# Preselector.net
KiCad netlist of a schematic drawn in EAGLE
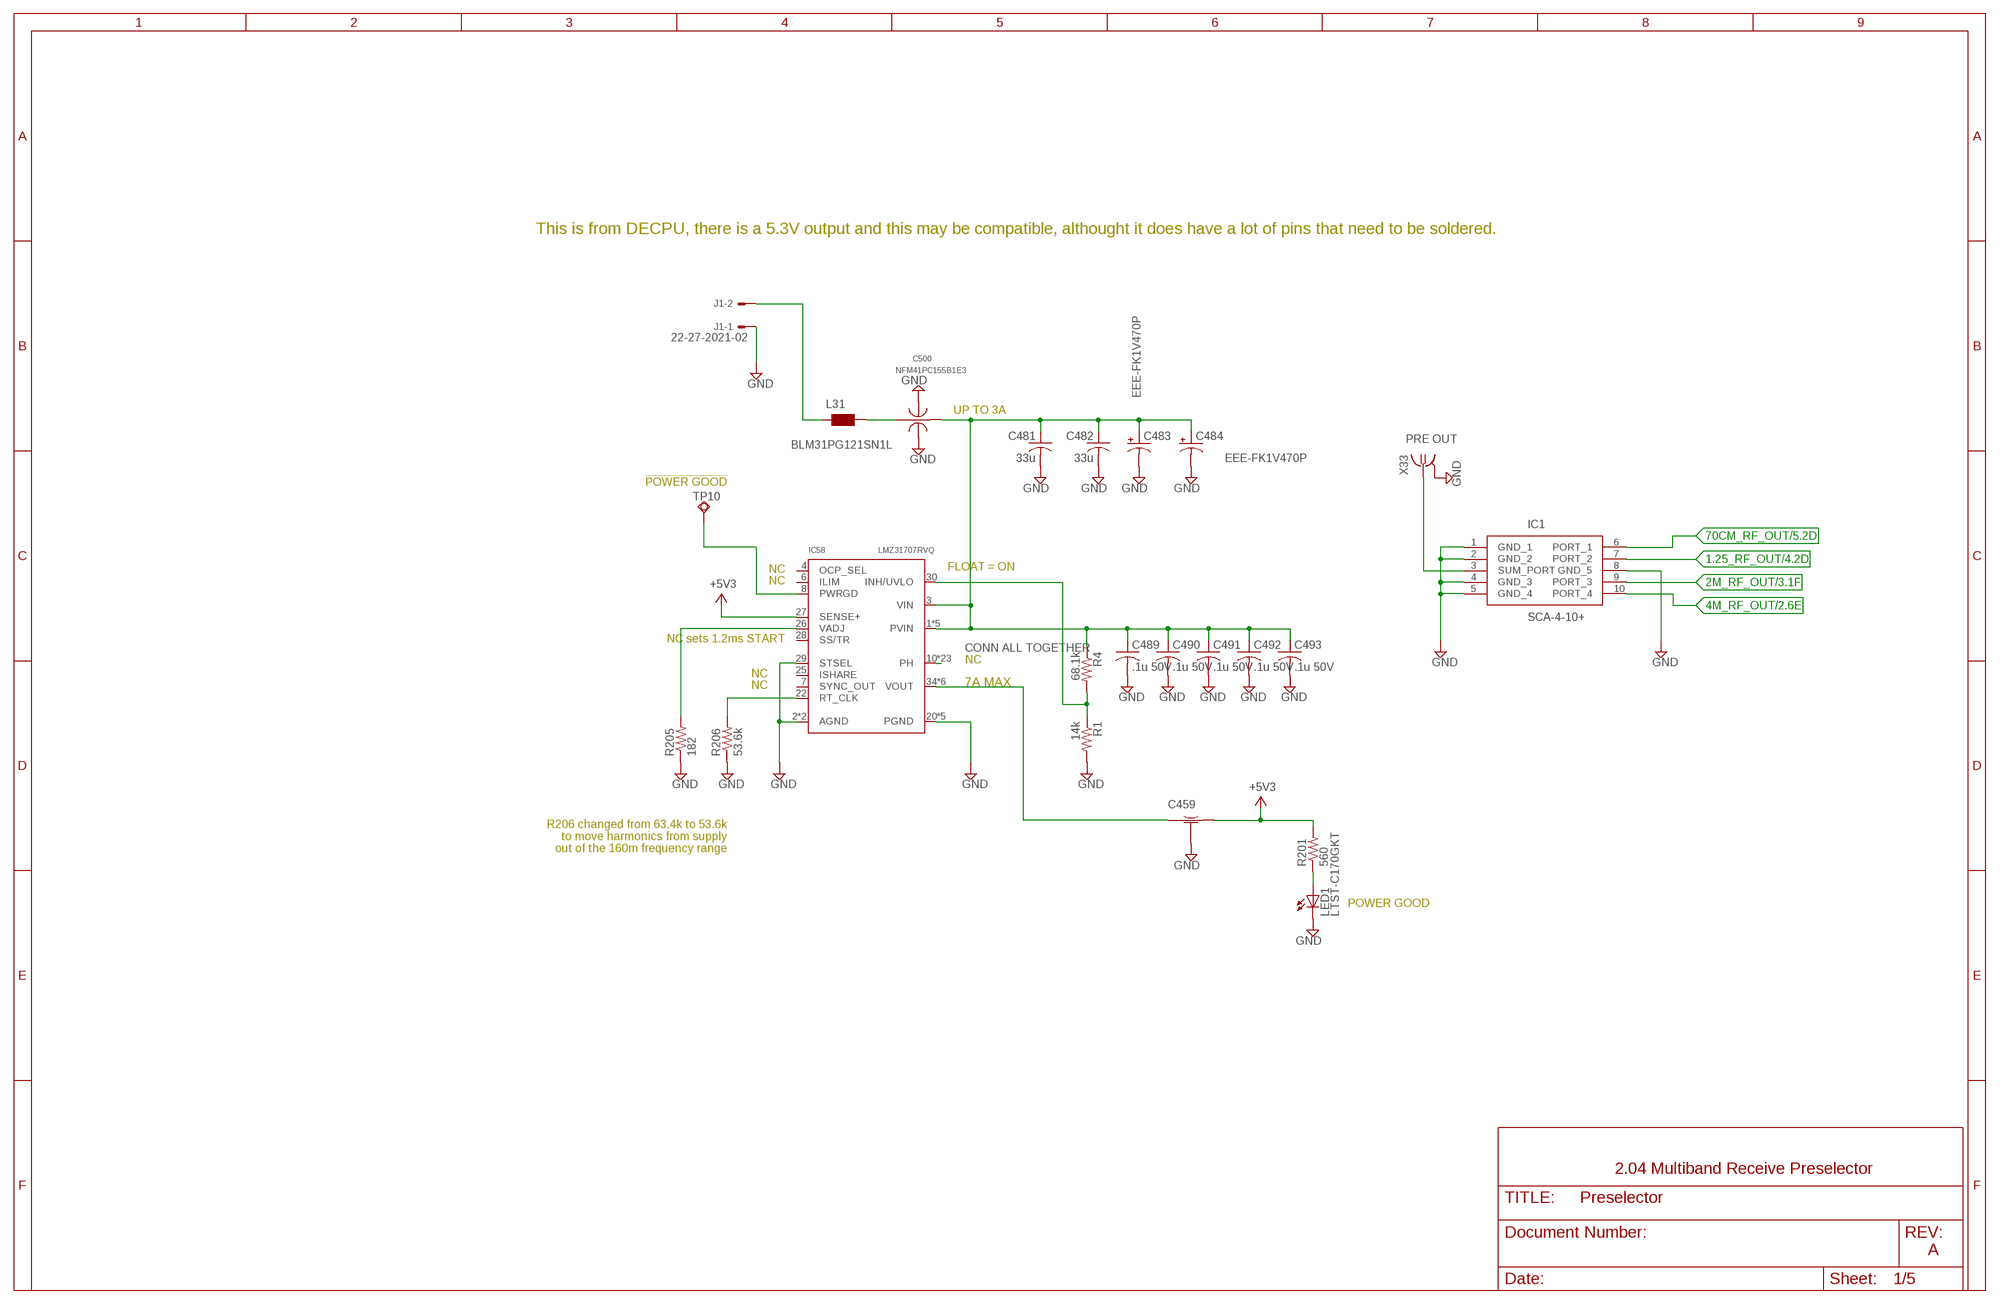
[diagram p0: schematic, sheet 1]
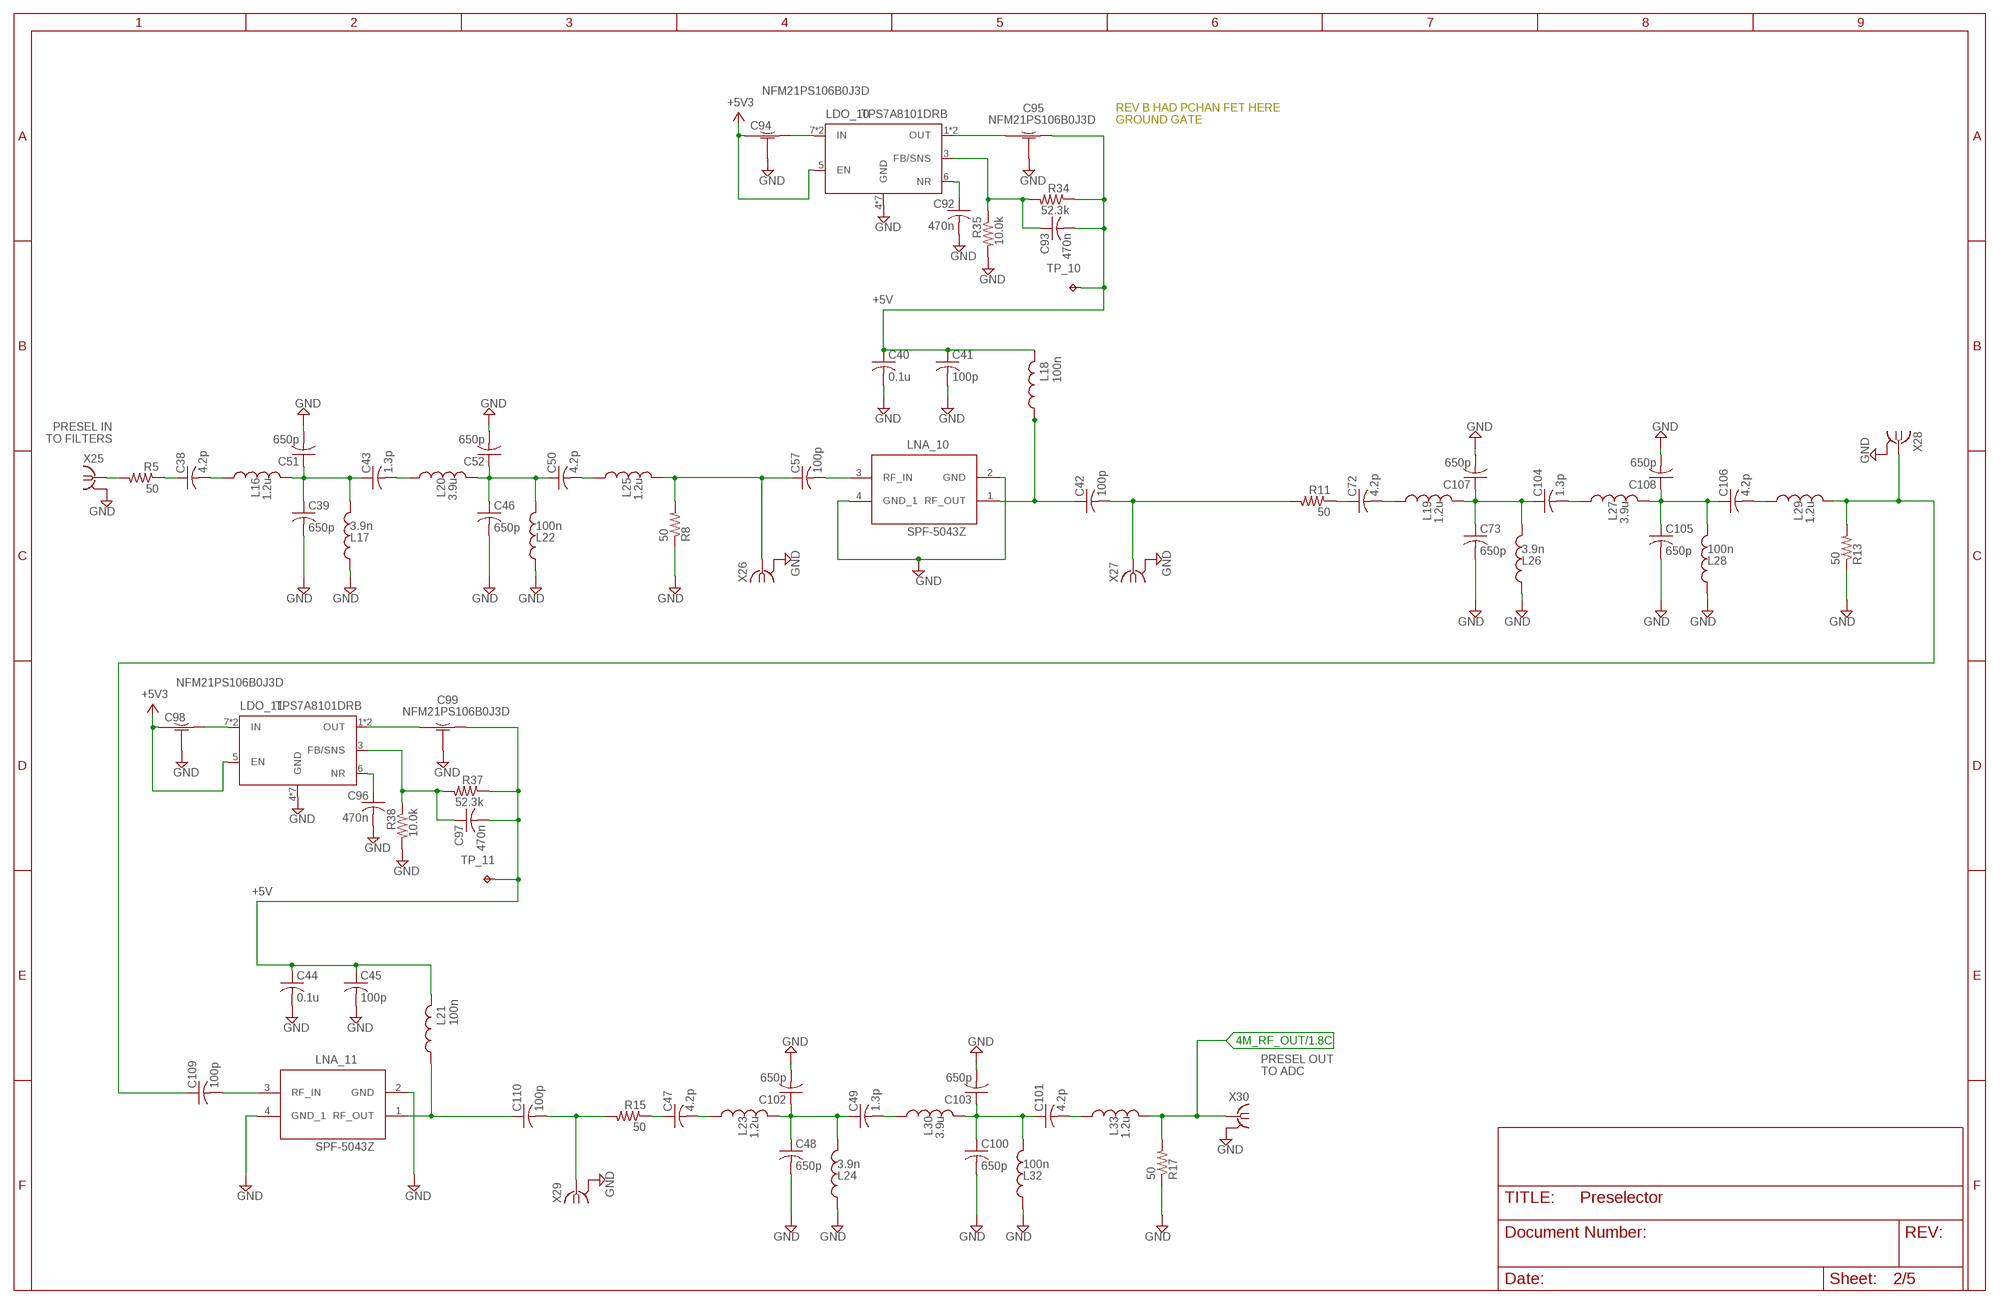
[diagram p1: schematic, sheet 2]
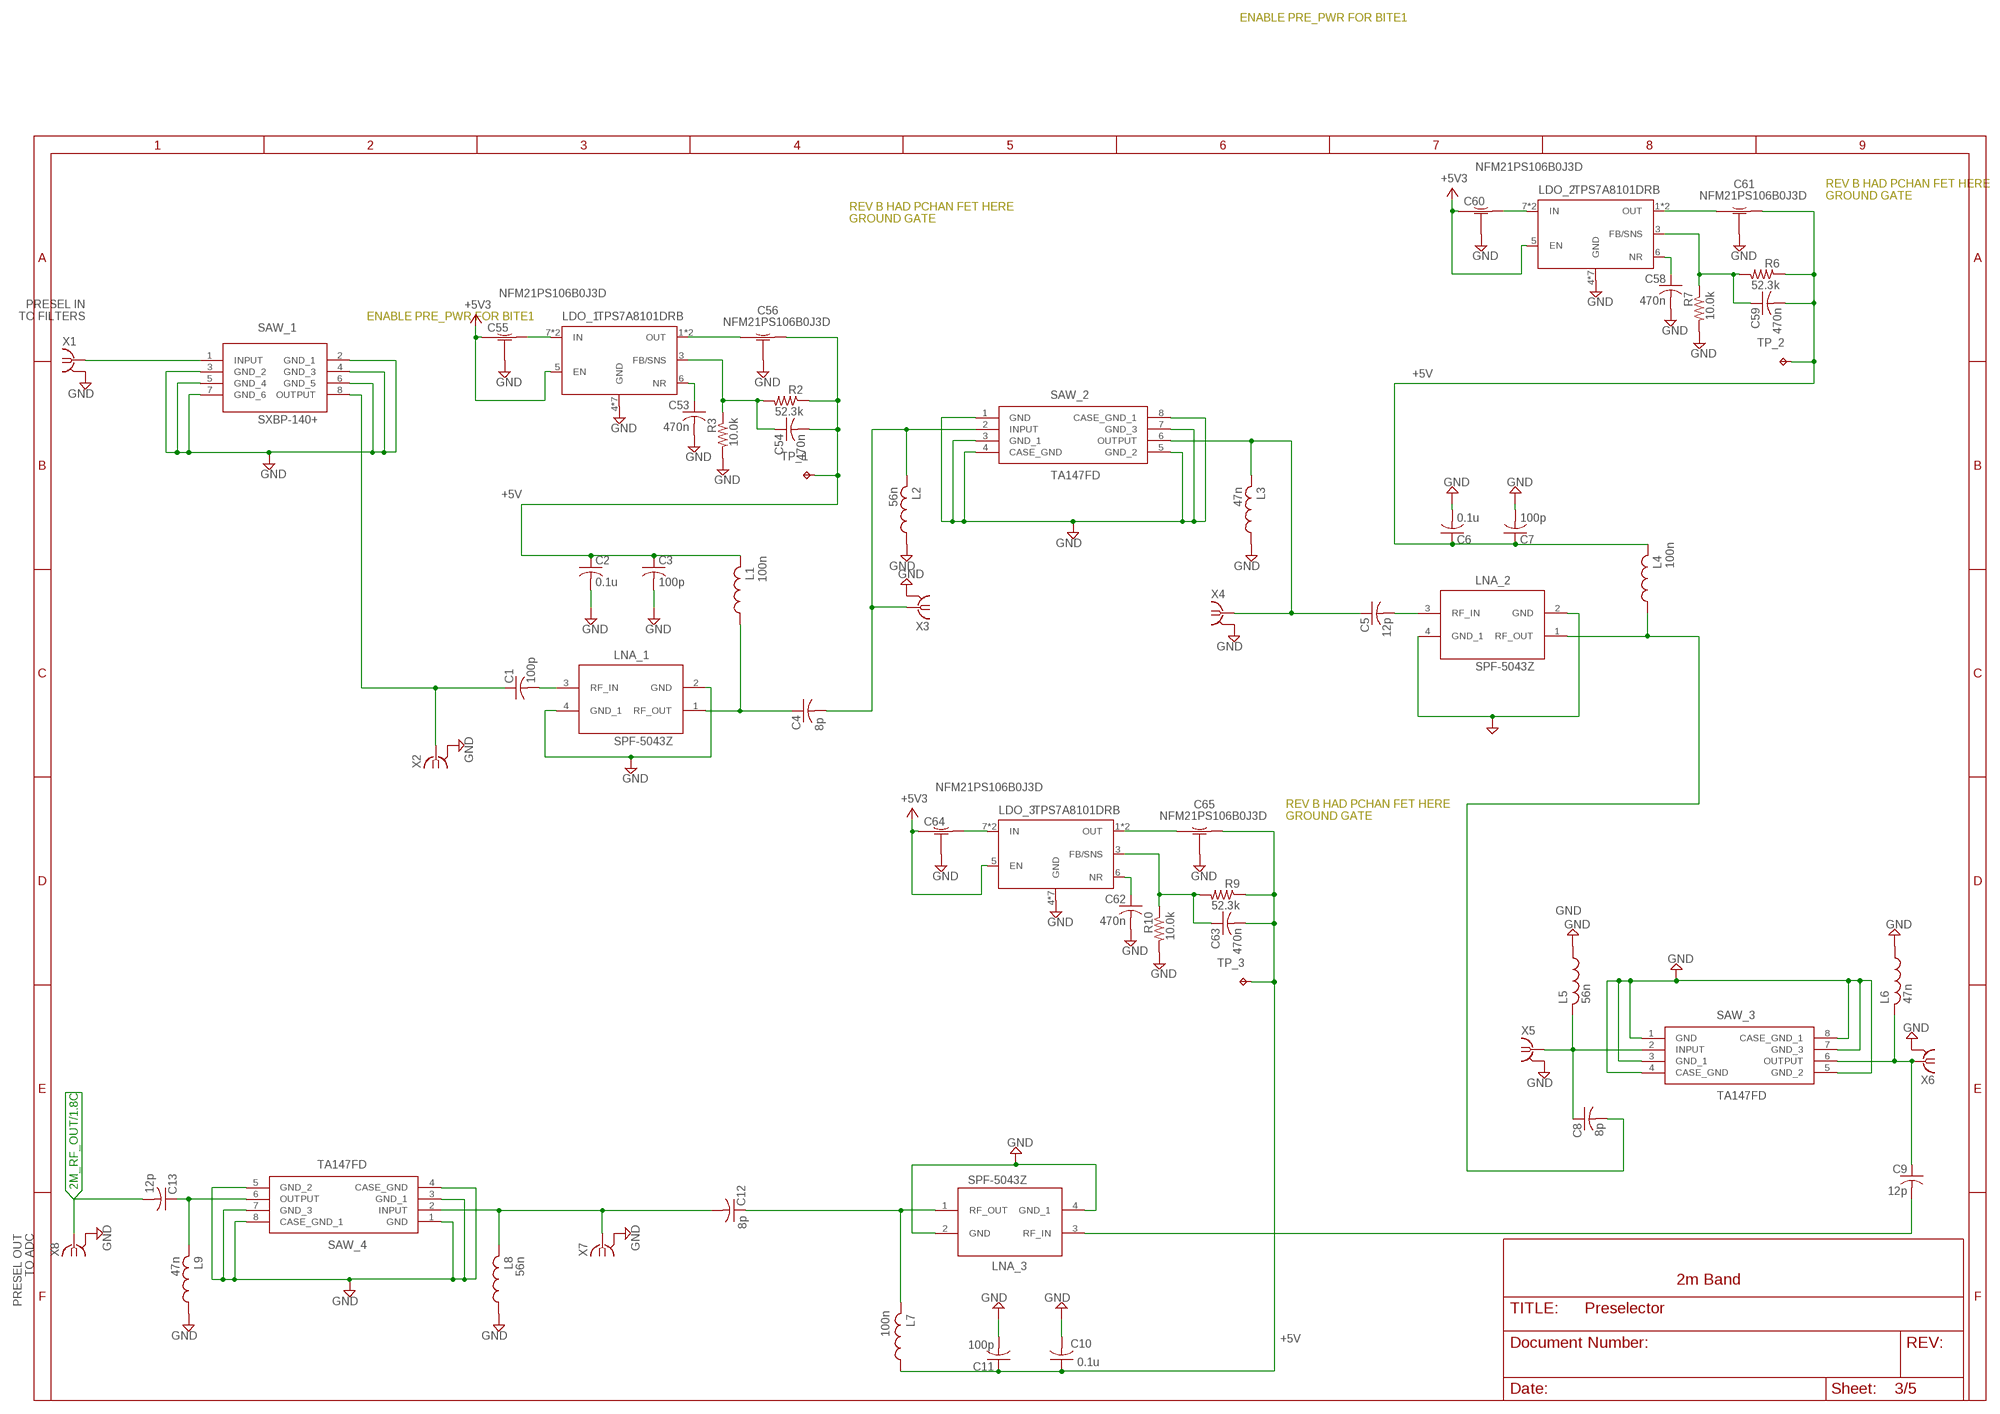
[diagram p2: schematic, sheet 3]
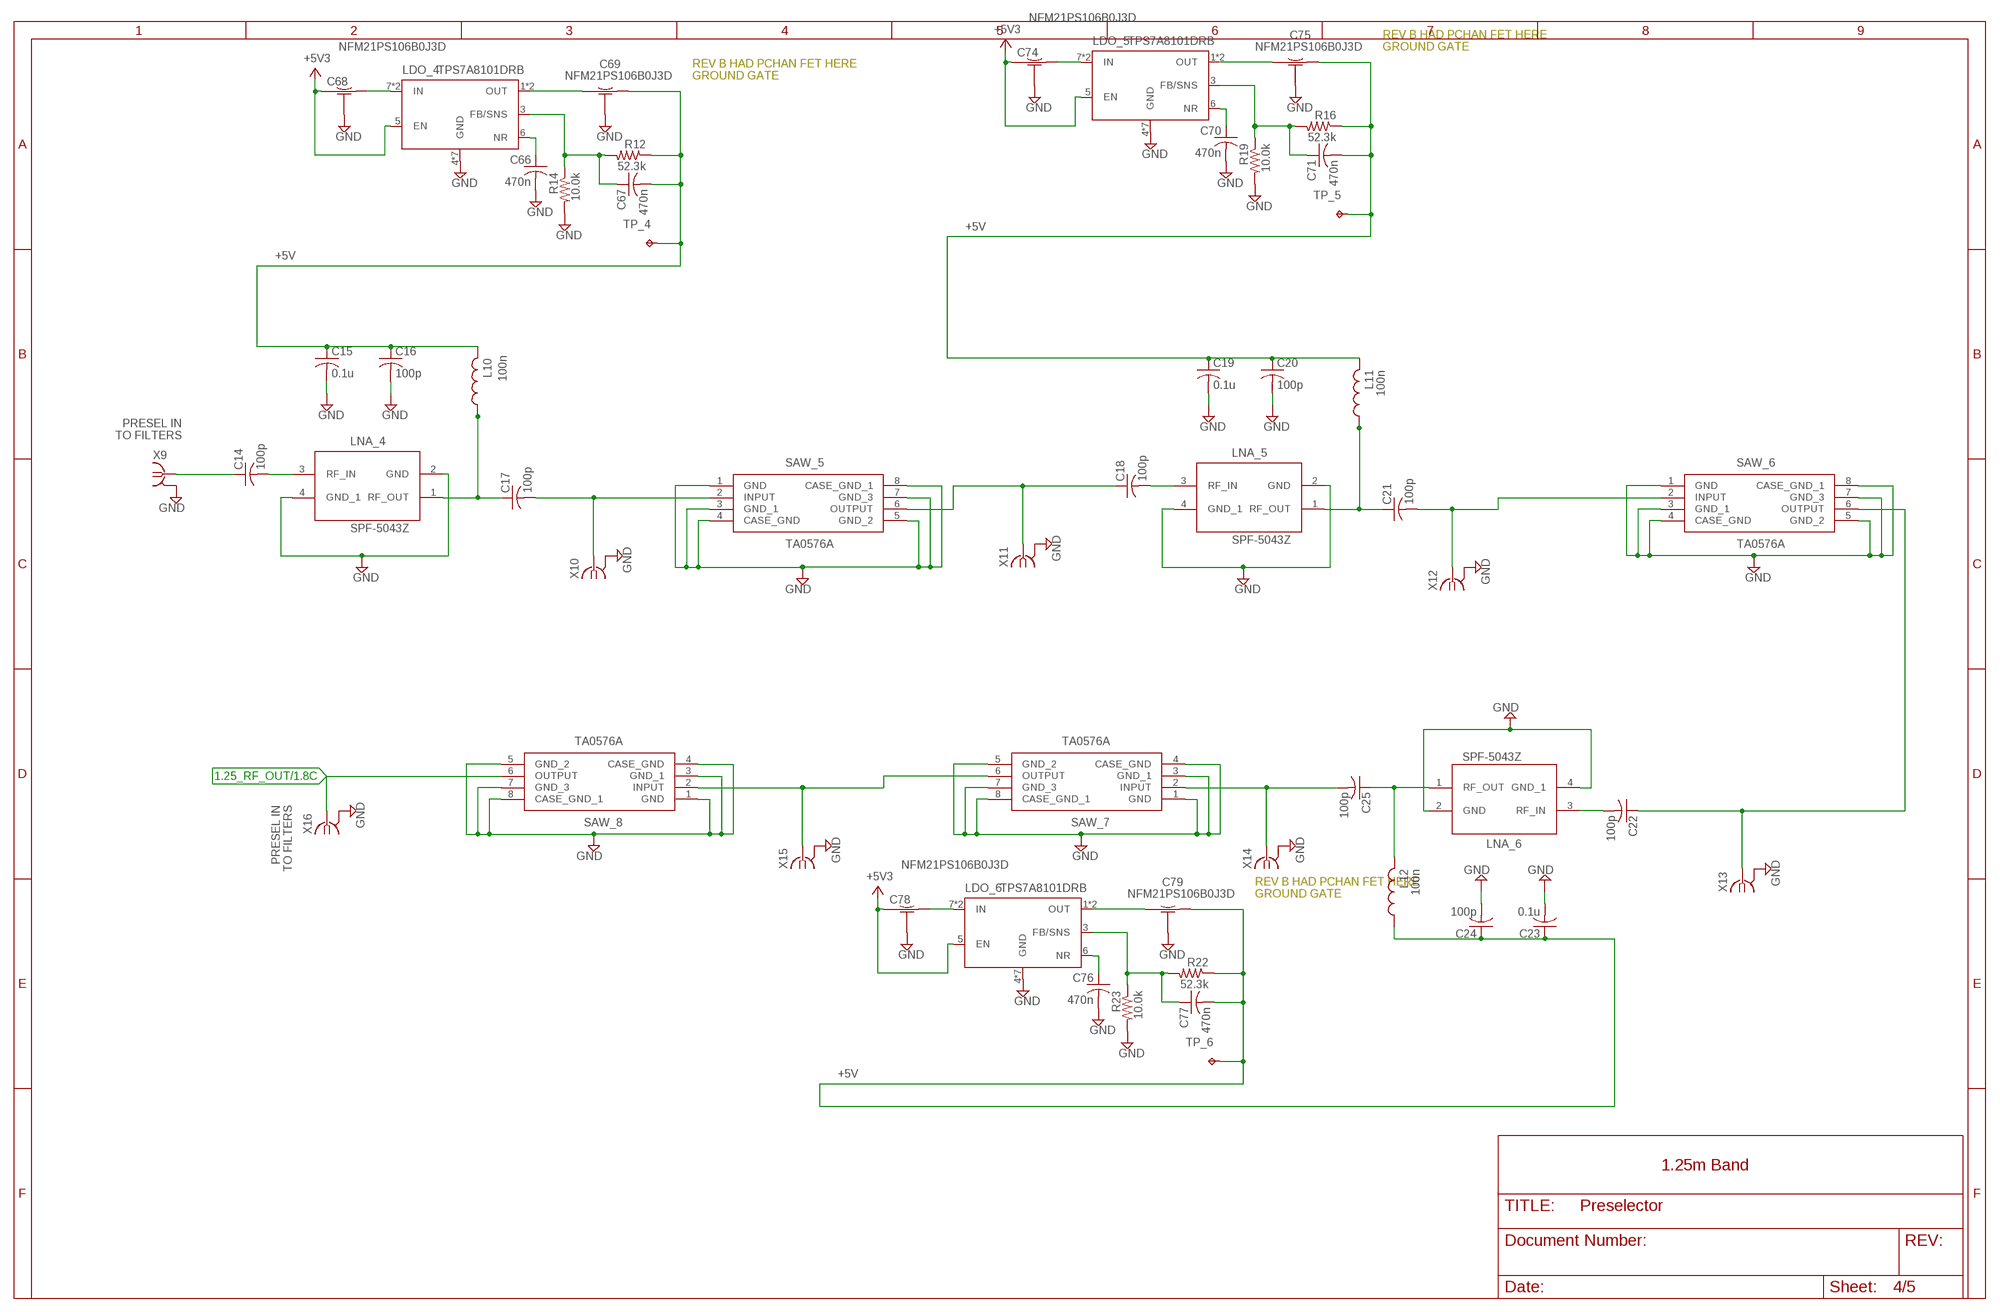
[diagram p3: schematic, sheet 4]
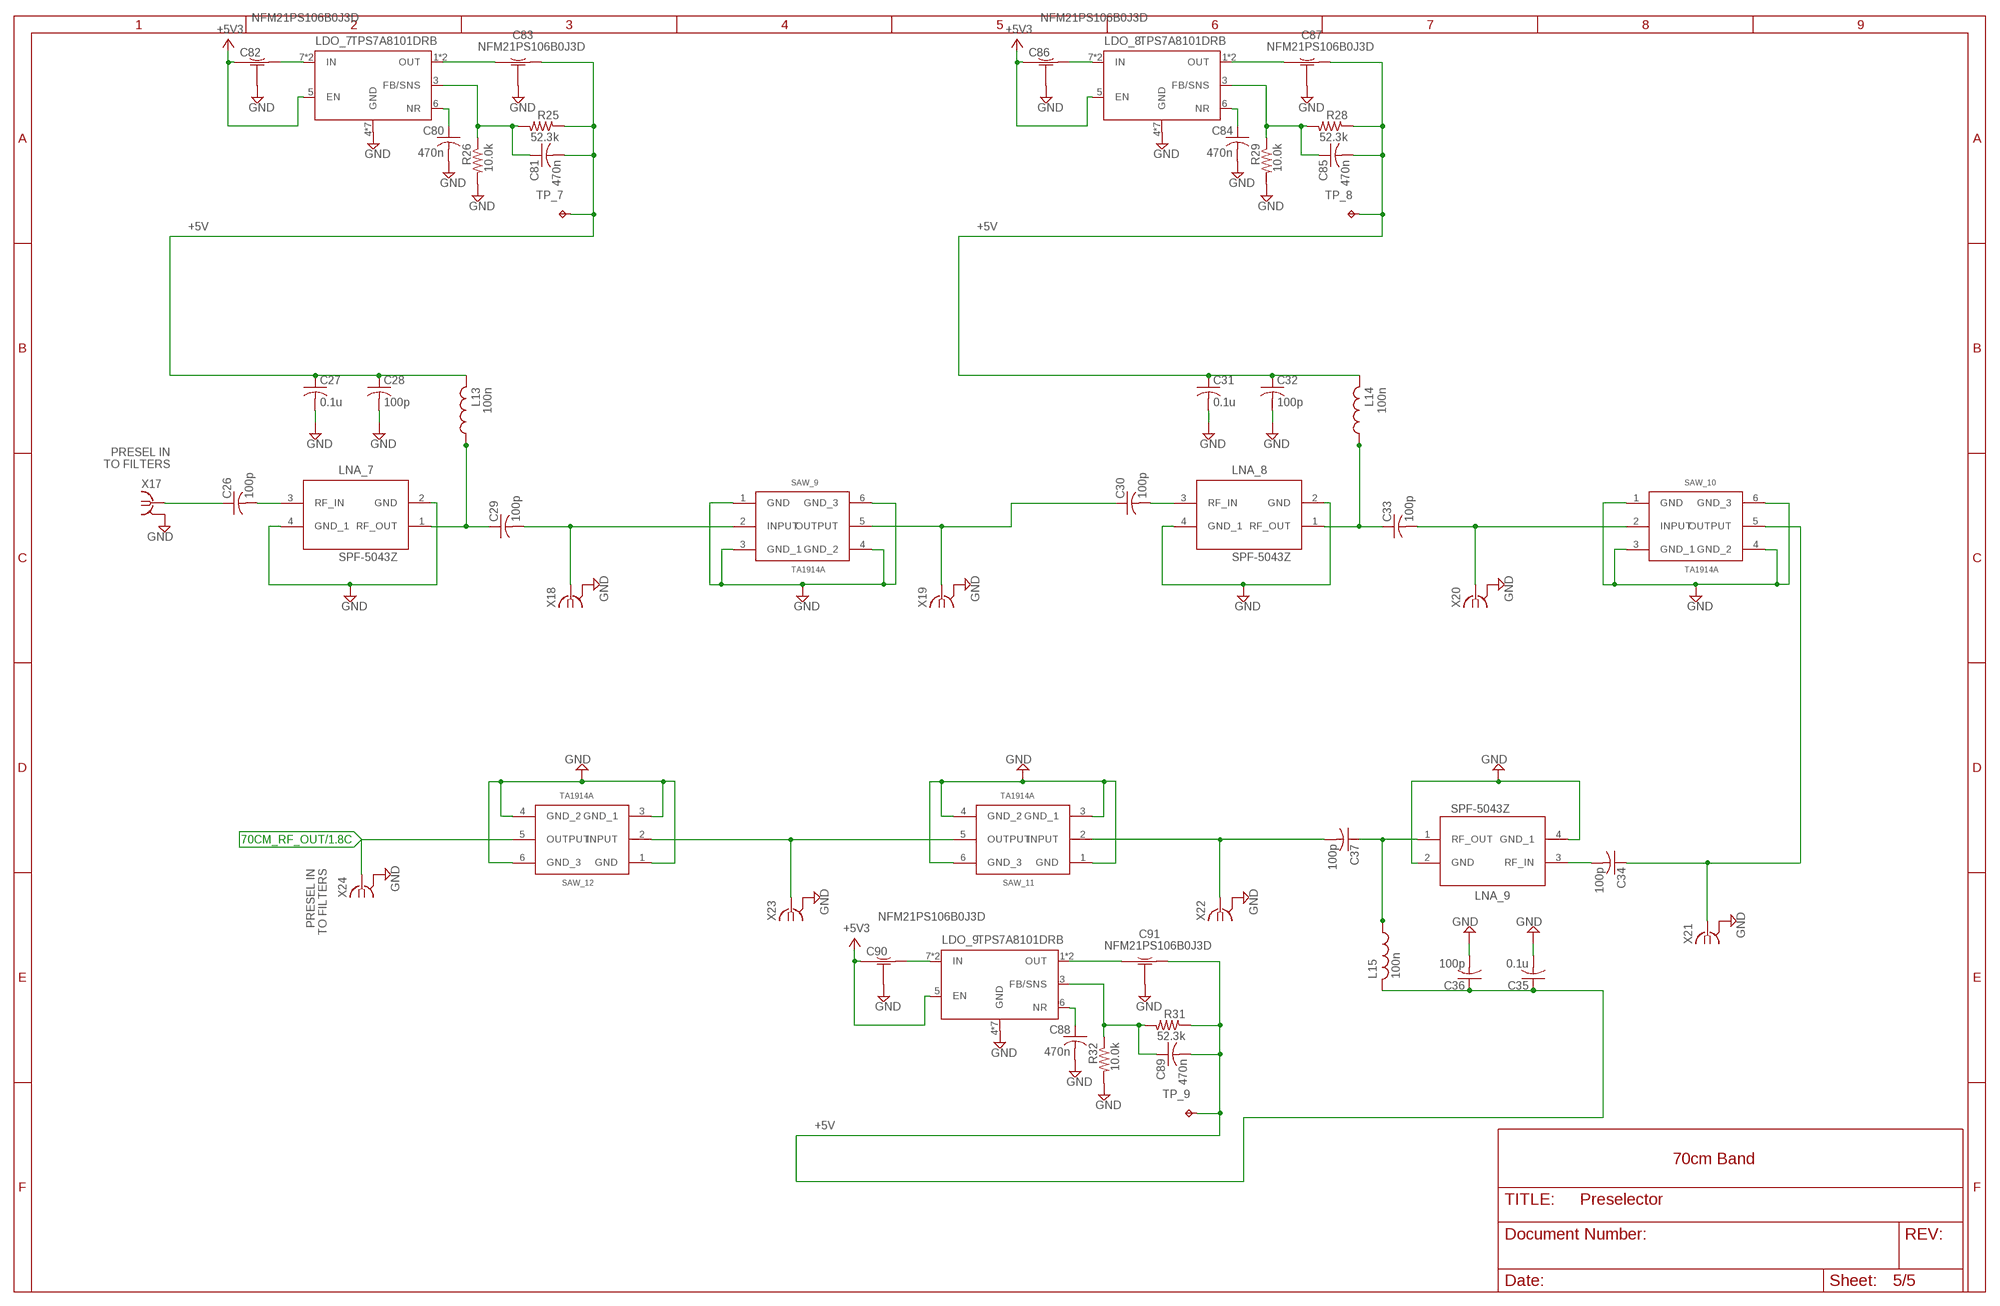
[diagram p4: schematic, sheet 5]

(export (version "E")
  (design (tool "Eeschema 10.0.6"))
  (components
    (comp (ref "C14")
      (value "100p")
      (footprint "eagle-import:C0603K")
      (libsource (lib "eagle-import") (part "C-USC0603K"))
    )
    (comp (ref "C15")
      (value "0.1u")
      (footprint "eagle-import:C0603K")
      (libsource (lib "eagle-import") (part "C-USC0603K"))
    )
    (comp (ref "C16")
      (value "100p")
      (footprint "eagle-import:C0603K")
      (libsource (lib "eagle-import") (part "C-USC0603K"))
    )
    (comp (ref "C17")
      (value "100p")
      (footprint "eagle-import:C0603K")
      (libsource (lib "eagle-import") (part "C-USC0603K"))
    )
    (comp (ref "C18")
      (value "100p")
      (footprint "eagle-import:C0603K")
      (libsource (lib "eagle-import") (part "C-USC0603K"))
    )
    (comp (ref "C19")
      (value "0.1u")
      (footprint "eagle-import:C0603K")
      (libsource (lib "eagle-import") (part "C-USC0603K"))
    )
    (comp (ref "C20")
      (value "100p")
      (footprint "eagle-import:C0603K")
      (libsource (lib "eagle-import") (part "C-USC0603K"))
    )
    (comp (ref "C21")
      (value "100p")
      (footprint "eagle-import:C0603K")
      (libsource (lib "eagle-import") (part "C-USC0603K"))
    )
    (comp (ref "C22")
      (value "100p")
      (footprint "eagle-import:C0603K")
      (libsource (lib "eagle-import") (part "C-USC0603K"))
    )
    (comp (ref "C23")
      (value "0.1u")
      (footprint "eagle-import:C0603K")
      (libsource (lib "eagle-import") (part "C-USC0603K"))
    )
    (comp (ref "C24")
      (value "100p")
      (footprint "eagle-import:C0603K")
      (libsource (lib "eagle-import") (part "C-USC0603K"))
    )
    (comp (ref "C25")
      (value "100p")
      (footprint "eagle-import:C0603K")
      (libsource (lib "eagle-import") (part "C-USC0603K"))
    )
    (comp (ref "C66")
      (value "470n")
      (footprint "eagle-import:C0603K")
      (libsource (lib "eagle-import") (part "C-USC0603K"))
    )
    (comp (ref "C67")
      (value "470n")
      (footprint "eagle-import:C0603K")
      (libsource (lib "eagle-import") (part "C-USC0603K"))
    )
    (comp (ref "C68")
      (value "NFM21PS106B0J3D")
      (footprint "eagle-import:NFM21PS")
      (libsource (lib "eagle-import") (part "NFM21PS"))
    )
    (comp (ref "C69")
      (value "NFM21PS106B0J3D")
      (footprint "eagle-import:NFM21PS")
      (libsource (lib "eagle-import") (part "NFM21PS"))
    )
    (comp (ref "C70")
      (value "470n")
      (footprint "eagle-import:C0603K")
      (libsource (lib "eagle-import") (part "C-USC0603K"))
    )
    (comp (ref "C71")
      (value "470n")
      (footprint "eagle-import:C0603K")
      (libsource (lib "eagle-import") (part "C-USC0603K"))
    )
    (comp (ref "C74")
      (value "NFM21PS106B0J3D")
      (footprint "eagle-import:NFM21PS")
      (libsource (lib "eagle-import") (part "NFM21PS"))
    )
    (comp (ref "C75")
      (value "NFM21PS106B0J3D")
      (footprint "eagle-import:NFM21PS")
      (libsource (lib "eagle-import") (part "NFM21PS"))
    )
    (comp (ref "C76")
      (value "470n")
      (footprint "eagle-import:C0603K")
      (libsource (lib "eagle-import") (part "C-USC0603K"))
    )
    (comp (ref "C77")
      (value "470n")
      (footprint "eagle-import:C0603K")
      (libsource (lib "eagle-import") (part "C-USC0603K"))
    )
    (comp (ref "C78")
      (value "NFM21PS106B0J3D")
      (footprint "eagle-import:NFM21PS")
      (libsource (lib "eagle-import") (part "NFM21PS"))
    )
    (comp (ref "C79")
      (value "NFM21PS106B0J3D")
      (footprint "eagle-import:NFM21PS")
      (libsource (lib "eagle-import") (part "NFM21PS"))
    )
    (comp (ref "L10")
      (value "100n")
      (footprint "eagle-import:C1206")
      (libsource (lib "eagle-import") (part "L-US1206"))
    )
    (comp (ref "L11")
      (value "100n")
      (footprint "eagle-import:C1206")
      (libsource (lib "eagle-import") (part "L-US1206"))
    )
    (comp (ref "L12")
      (value "100n")
      (footprint "eagle-import:C1206")
      (libsource (lib "eagle-import") (part "L-US1206"))
    )
    (comp (ref "LDO_4")
      (value "TPS7A8101DRB")
      (footprint "eagle-import:DRB")
      (libsource (lib "eagle-import") (part "TPS7A8101DRB"))
    )
    (comp (ref "LDO_5")
      (value "TPS7A8101DRB")
      (footprint "eagle-import:DRB")
      (libsource (lib "eagle-import") (part "TPS7A8101DRB"))
    )
    (comp (ref "LDO_6")
      (value "TPS7A8101DRB")
      (footprint "eagle-import:DRB")
      (libsource (lib "eagle-import") (part "TPS7A8101DRB"))
    )
    (comp (ref "LNA_4")
      (value "SPF-5043Z")
      (footprint "eagle-import:SPF-5043Z")
      (libsource (lib "eagle-import") (part "SPF-5043Z"))
    )
    (comp (ref "LNA_5")
      (value "SPF-5043Z")
      (footprint "eagle-import:SPF-5043Z")
      (libsource (lib "eagle-import") (part "SPF-5043Z"))
    )
    (comp (ref "LNA_6")
      (value "SPF-5043Z")
      (footprint "eagle-import:SPF-5043Z")
      (libsource (lib "eagle-import") (part "SPF-5043Z"))
    )
    (comp (ref "R12")
      (value "52.3k")
      (footprint "eagle-import:R0603")
      (libsource (lib "eagle-import") (part "R-US_R0603"))
    )
    (comp (ref "R14")
      (value "10.0k")
      (footprint "eagle-import:R0603")
      (libsource (lib "eagle-import") (part "R-US_R0603"))
    )
    (comp (ref "R16")
      (value "52.3k")
      (footprint "eagle-import:R0603")
      (libsource (lib "eagle-import") (part "R-US_R0603"))
    )
    (comp (ref "R19")
      (value "10.0k")
      (footprint "eagle-import:R0603")
      (libsource (lib "eagle-import") (part "R-US_R0603"))
    )
    (comp (ref "R22")
      (value "52.3k")
      (footprint "eagle-import:R0603")
      (libsource (lib "eagle-import") (part "R-US_R0603"))
    )
    (comp (ref "R23")
      (value "10.0k")
      (footprint "eagle-import:R0603")
      (libsource (lib "eagle-import") (part "R-US_R0603"))
    )
    (comp (ref "SAW_5")
      (value "TA0576A")
      (footprint "eagle-import:TA0576A")
      (libsource (lib "eagle-import") (part "TA0576A"))
    )
    (comp (ref "SAW_6")
      (value "TA0576A")
      (footprint "eagle-import:TA0576A")
      (libsource (lib "eagle-import") (part "TA0576A"))
    )
    (comp (ref "SAW_7")
      (value "TA0576A")
      (footprint "eagle-import:TA0576A")
      (libsource (lib "eagle-import") (part "TA0576A"))
    )
    (comp (ref "SAW_8")
      (value "TA0576A")
      (footprint "eagle-import:TA0576A")
      (libsource (lib "eagle-import") (part "TA0576A"))
    )
    (comp (ref "TP_4")
      (value "TPTP20SQ")
      (footprint "eagle-import:TP20SQ")
      (libsource (lib "eagle-import") (part "TPTP20SQ"))
    )
    (comp (ref "TP_5")
      (value "TPTP20SQ")
      (footprint "eagle-import:TP20SQ")
      (libsource (lib "eagle-import") (part "TPTP20SQ"))
    )
    (comp (ref "TP_6")
      (value "TPTP20SQ")
      (footprint "eagle-import:TP20SQ")
      (libsource (lib "eagle-import") (part "TPTP20SQ"))
    )
    (comp (ref "X9")
      (value "0733660061")
      (footprint "eagle-import:BU-SMA-V")
      (libsource (lib "eagle-import") (part "BU-SMA-V"))
    )
    (comp (ref "X10")
      (value "0733660061")
      (footprint "eagle-import:BU-SMA-V")
      (libsource (lib "eagle-import") (part "BU-SMA-V"))
    )
    (comp (ref "X11")
      (value "0733660061")
      (footprint "eagle-import:BU-SMA-V")
      (libsource (lib "eagle-import") (part "BU-SMA-V"))
    )
    (comp (ref "X12")
      (value "0733660061")
      (footprint "eagle-import:BU-SMA-V")
      (libsource (lib "eagle-import") (part "BU-SMA-V"))
    )
    (comp (ref "X13")
      (value "0733660061")
      (footprint "eagle-import:BU-SMA-V")
      (libsource (lib "eagle-import") (part "BU-SMA-V"))
    )
    (comp (ref "X14")
      (value "0733660061")
      (footprint "eagle-import:BU-SMA-V")
      (libsource (lib "eagle-import") (part "BU-SMA-V"))
    )
    (comp (ref "X15")
      (value "0733660061")
      (footprint "eagle-import:BU-SMA-V")
      (libsource (lib "eagle-import") (part "BU-SMA-V"))
    )
    (comp (ref "X16")
      (value "0733660061")
      (footprint "eagle-import:BU-SMA-V")
      (libsource (lib "eagle-import") (part "BU-SMA-V"))
    )
    (comp (ref "C38")
      (value "4.2p")
      (footprint "eagle-import:C0603K")
      (libsource (lib "eagle-import") (part "C-USC0603K"))
    )
    (comp (ref "C39")
      (value "650p")
      (footprint "eagle-import:C0603K")
      (libsource (lib "eagle-import") (part "C-USC0603K"))
    )
    (comp (ref "C40")
      (value "0.1u")
      (footprint "eagle-import:C0603K")
      (libsource (lib "eagle-import") (part "C-USC0603K"))
    )
    (comp (ref "C41")
      (value "100p")
      (footprint "eagle-import:C0603K")
      (libsource (lib "eagle-import") (part "C-USC0603K"))
    )
    (comp (ref "C42")
      (value "100p")
      (footprint "eagle-import:C0603K")
      (libsource (lib "eagle-import") (part "C-USC0603K"))
    )
    (comp (ref "C43")
      (value "1.3p")
      (footprint "eagle-import:C0603K")
      (libsource (lib "eagle-import") (part "C-USC0603K"))
    )
    (comp (ref "C44")
      (value "0.1u")
      (footprint "eagle-import:C0603K")
      (libsource (lib "eagle-import") (part "C-USC0603K"))
    )
    (comp (ref "C45")
      (value "100p")
      (footprint "eagle-import:C0603K")
      (libsource (lib "eagle-import") (part "C-USC0603K"))
    )
    (comp (ref "C46")
      (value "650p")
      (footprint "eagle-import:C0603K")
      (libsource (lib "eagle-import") (part "C-USC0603K"))
    )
    (comp (ref "C47")
      (value "4.2p")
      (footprint "eagle-import:C0603K")
      (libsource (lib "eagle-import") (part "C-USC0603K"))
    )
    (comp (ref "C48")
      (value "650p")
      (footprint "eagle-import:C0603K")
      (libsource (lib "eagle-import") (part "C-USC0603K"))
    )
    (comp (ref "C49")
      (value "1.3p")
      (footprint "eagle-import:C0603K")
      (libsource (lib "eagle-import") (part "C-USC0603K"))
    )
    (comp (ref "C50")
      (value "4.2p")
      (footprint "eagle-import:C0603K")
      (libsource (lib "eagle-import") (part "C-USC0603K"))
    )
    (comp (ref "C51")
      (value "650p")
      (footprint "eagle-import:C0603K")
      (libsource (lib "eagle-import") (part "C-USC0603K"))
    )
    (comp (ref "C52")
      (value "650p")
      (footprint "eagle-import:C0603K")
      (libsource (lib "eagle-import") (part "C-USC0603K"))
    )
    (comp (ref "C57")
      (value "100p")
      (footprint "eagle-import:C0603K")
      (libsource (lib "eagle-import") (part "C-USC0603K"))
    )
    (comp (ref "C72")
      (value "4.2p")
      (footprint "eagle-import:C0603K")
      (libsource (lib "eagle-import") (part "C-USC0603K"))
    )
    (comp (ref "C73")
      (value "650p")
      (footprint "eagle-import:C0603K")
      (libsource (lib "eagle-import") (part "C-USC0603K"))
    )
    (comp (ref "C92")
      (value "470n")
      (footprint "eagle-import:C0603K")
      (libsource (lib "eagle-import") (part "C-USC0603K"))
    )
    (comp (ref "C93")
      (value "470n")
      (footprint "eagle-import:C0603K")
      (libsource (lib "eagle-import") (part "C-USC0603K"))
    )
    (comp (ref "C94")
      (value "NFM21PS106B0J3D")
      (footprint "eagle-import:NFM21PS")
      (libsource (lib "eagle-import") (part "NFM21PS"))
    )
    (comp (ref "C95")
      (value "NFM21PS106B0J3D")
      (footprint "eagle-import:NFM21PS")
      (libsource (lib "eagle-import") (part "NFM21PS"))
    )
    (comp (ref "C96")
      (value "470n")
      (footprint "eagle-import:C0603K")
      (libsource (lib "eagle-import") (part "C-USC0603K"))
    )
    (comp (ref "C97")
      (value "470n")
      (footprint "eagle-import:C0603K")
      (libsource (lib "eagle-import") (part "C-USC0603K"))
    )
    (comp (ref "C98")
      (value "NFM21PS106B0J3D")
      (footprint "eagle-import:NFM21PS")
      (libsource (lib "eagle-import") (part "NFM21PS"))
    )
    (comp (ref "C99")
      (value "NFM21PS106B0J3D")
      (footprint "eagle-import:NFM21PS")
      (libsource (lib "eagle-import") (part "NFM21PS"))
    )
    (comp (ref "C100")
      (value "650p")
      (footprint "eagle-import:C0603K")
      (libsource (lib "eagle-import") (part "C-USC0603K"))
    )
    (comp (ref "C101")
      (value "4.2p")
      (footprint "eagle-import:C0603K")
      (libsource (lib "eagle-import") (part "C-USC0603K"))
    )
    (comp (ref "C102")
      (value "650p")
      (footprint "eagle-import:C0603K")
      (libsource (lib "eagle-import") (part "C-USC0603K"))
    )
    (comp (ref "C103")
      (value "650p")
      (footprint "eagle-import:C0603K")
      (libsource (lib "eagle-import") (part "C-USC0603K"))
    )
    (comp (ref "C104")
      (value "1.3p")
      (footprint "eagle-import:C0603K")
      (libsource (lib "eagle-import") (part "C-USC0603K"))
    )
    (comp (ref "C105")
      (value "650p")
      (footprint "eagle-import:C0603K")
      (libsource (lib "eagle-import") (part "C-USC0603K"))
    )
    (comp (ref "C106")
      (value "4.2p")
      (footprint "eagle-import:C0603K")
      (libsource (lib "eagle-import") (part "C-USC0603K"))
    )
    (comp (ref "C107")
      (value "650p")
      (footprint "eagle-import:C0603K")
      (libsource (lib "eagle-import") (part "C-USC0603K"))
    )
    (comp (ref "C108")
      (value "650p")
      (footprint "eagle-import:C0603K")
      (libsource (lib "eagle-import") (part "C-USC0603K"))
    )
    (comp (ref "C109")
      (value "100p")
      (footprint "eagle-import:C0603K")
      (libsource (lib "eagle-import") (part "C-USC0603K"))
    )
    (comp (ref "C110")
      (value "100p")
      (footprint "eagle-import:C0603K")
      (libsource (lib "eagle-import") (part "C-USC0603K"))
    )
    (comp (ref "L16")
      (value "1.2u")
      (footprint "eagle-import:C0603K")
      (libsource (lib "eagle-import") (part "L-US0603"))
    )
    (comp (ref "L17")
      (value "3.9n")
      (footprint "eagle-import:C0603K")
      (libsource (lib "eagle-import") (part "L-US0603"))
    )
    (comp (ref "L18")
      (value "100n")
      (footprint "eagle-import:C1206")
      (libsource (lib "eagle-import") (part "L-US1206"))
    )
    (comp (ref "L19")
      (value "1.2u")
      (footprint "eagle-import:C0603K")
      (libsource (lib "eagle-import") (part "L-US0603"))
    )
    (comp (ref "L20")
      (value "3.9u")
      (footprint "eagle-import:C0603K")
      (libsource (lib "eagle-import") (part "L-US0603"))
    )
    (comp (ref "L21")
      (value "100n")
      (footprint "eagle-import:C1206")
      (libsource (lib "eagle-import") (part "L-US1206"))
    )
    (comp (ref "L22")
      (value "100n")
      (footprint "eagle-import:C0603K")
      (libsource (lib "eagle-import") (part "L-US0603"))
    )
    (comp (ref "L23")
      (value "1.2u")
      (footprint "eagle-import:C0603K")
      (libsource (lib "eagle-import") (part "L-US0603"))
    )
    (comp (ref "L24")
      (value "3.9n")
      (footprint "eagle-import:C0603K")
      (libsource (lib "eagle-import") (part "L-US0603"))
    )
    (comp (ref "L25")
      (value "1.2u")
      (footprint "eagle-import:C0603K")
      (libsource (lib "eagle-import") (part "L-US0603"))
    )
    (comp (ref "L26")
      (value "3.9n")
      (footprint "eagle-import:C0603K")
      (libsource (lib "eagle-import") (part "L-US0603"))
    )
    (comp (ref "L27")
      (value "3.9u")
      (footprint "eagle-import:C0603K")
      (libsource (lib "eagle-import") (part "L-US0603"))
    )
    (comp (ref "L28")
      (value "100n")
      (footprint "eagle-import:C0603K")
      (libsource (lib "eagle-import") (part "L-US0603"))
    )
    (comp (ref "L29")
      (value "1.2u")
      (footprint "eagle-import:C0603K")
      (libsource (lib "eagle-import") (part "L-US0603"))
    )
    (comp (ref "L30")
      (value "3.9u")
      (footprint "eagle-import:C0603K")
      (libsource (lib "eagle-import") (part "L-US0603"))
    )
    (comp (ref "L32")
      (value "100n")
      (footprint "eagle-import:C0603K")
      (libsource (lib "eagle-import") (part "L-US0603"))
    )
    (comp (ref "L33")
      (value "1.2u")
      (footprint "eagle-import:C0603K")
      (libsource (lib "eagle-import") (part "L-US0603"))
    )
    (comp (ref "LDO_10")
      (value "TPS7A8101DRB")
      (footprint "eagle-import:DRB")
      (libsource (lib "eagle-import") (part "TPS7A8101DRB"))
    )
    (comp (ref "LDO_11")
      (value "TPS7A8101DRB")
      (footprint "eagle-import:DRB")
      (libsource (lib "eagle-import") (part "TPS7A8101DRB"))
    )
    (comp (ref "LNA_10")
      (value "SPF-5043Z")
      (footprint "eagle-import:SPF-5043Z")
      (libsource (lib "eagle-import") (part "SPF-5043Z"))
    )
    (comp (ref "LNA_11")
      (value "SPF-5043Z")
      (footprint "eagle-import:SPF-5043Z")
      (libsource (lib "eagle-import") (part "SPF-5043Z"))
    )
    (comp (ref "R5")
      (value "50")
      (footprint "eagle-import:R0603")
      (libsource (lib "eagle-import") (part "R-US_R0603"))
    )
    (comp (ref "R8")
      (value "50")
      (footprint "eagle-import:R0603")
      (libsource (lib "eagle-import") (part "R-US_R0603"))
    )
    (comp (ref "R11")
      (value "50")
      (footprint "eagle-import:R0603")
      (libsource (lib "eagle-import") (part "R-US_R0603"))
    )
    (comp (ref "R13")
      (value "50")
      (footprint "eagle-import:R0603")
      (libsource (lib "eagle-import") (part "R-US_R0603"))
    )
    (comp (ref "R15")
      (value "50")
      (footprint "eagle-import:R0603")
      (libsource (lib "eagle-import") (part "R-US_R0603"))
    )
    (comp (ref "R17")
      (value "50")
      (footprint "eagle-import:R0603")
      (libsource (lib "eagle-import") (part "R-US_R0603"))
    )
    (comp (ref "R34")
      (value "52.3k")
      (footprint "eagle-import:R0603")
      (libsource (lib "eagle-import") (part "R-US_R0603"))
    )
    (comp (ref "R35")
      (value "10.0k")
      (footprint "eagle-import:R0603")
      (libsource (lib "eagle-import") (part "R-US_R0603"))
    )
    (comp (ref "R37")
      (value "52.3k")
      (footprint "eagle-import:R0603")
      (libsource (lib "eagle-import") (part "R-US_R0603"))
    )
    (comp (ref "R38")
      (value "10.0k")
      (footprint "eagle-import:R0603")
      (libsource (lib "eagle-import") (part "R-US_R0603"))
    )
    (comp (ref "TP_10")
      (value "TPTP20SQ")
      (footprint "eagle-import:TP20SQ")
      (libsource (lib "eagle-import") (part "TPTP20SQ"))
    )
    (comp (ref "TP_11")
      (value "TPTP20SQ")
      (footprint "eagle-import:TP20SQ")
      (libsource (lib "eagle-import") (part "TPTP20SQ"))
    )
    (comp (ref "X25")
      (value "0733660061")
      (footprint "eagle-import:BU-SMA-V")
      (libsource (lib "eagle-import") (part "BU-SMA-V"))
    )
    (comp (ref "X26")
      (value "0733660061")
      (footprint "eagle-import:BU-SMA-V")
      (libsource (lib "eagle-import") (part "BU-SMA-V"))
    )
    (comp (ref "X27")
      (value "0733660061")
      (footprint "eagle-import:BU-SMA-V")
      (libsource (lib "eagle-import") (part "BU-SMA-V"))
    )
    (comp (ref "X28")
      (value "0733660061")
      (footprint "eagle-import:BU-SMA-V")
      (libsource (lib "eagle-import") (part "BU-SMA-V"))
    )
    (comp (ref "X29")
      (value "0733660061")
      (footprint "eagle-import:BU-SMA-V")
      (libsource (lib "eagle-import") (part "BU-SMA-V"))
    )
    (comp (ref "X30")
      (value "0733660061")
      (footprint "eagle-import:BU-SMA-V")
      (libsource (lib "eagle-import") (part "BU-SMA-V"))
    )
    (comp (ref "C459")
      (value "NFM31PC276B0J3L")
      (footprint "eagle-import:NFM31PC276")
      (libsource (lib "eagle-import") (part "NFM31PC276B0J3L"))
    )
    (comp (ref "C481")
      (value "33u")
      (footprint "eagle-import:C1206K")
      (libsource (lib "eagle-import") (part "C-USC1206K"))
    )
    (comp (ref "C482")
      (value "33u")
      (footprint "eagle-import:C1206K")
      (libsource (lib "eagle-import") (part "C-USC1206K"))
    )
    (comp (ref "C483")
      (value "EEE-FK1V470P")
      (footprint "eagle-import:PANASONIC_D")
      (fields (field (name "PN") "EEE-FK1V470P"))
      (libsource (lib "eagle-import") (part "CPOL-USD"))
    )
    (comp (ref "C484")
      (value "EEE-FK1V470P")
      (footprint "eagle-import:PANASONIC_D")
      (fields (field (name "PN") "EEE-FK1V470P"))
      (libsource (lib "eagle-import") (part "CPOL-USD"))
    )
    (comp (ref "C489")
      (value ".1u 50V")
      (footprint "eagle-import:C0603K")
      (libsource (lib "eagle-import") (part "C-USC0603K"))
    )
    (comp (ref "C490")
      (value ".1u 50V")
      (footprint "eagle-import:C0603K")
      (libsource (lib "eagle-import") (part "C-USC0603K"))
    )
    (comp (ref "C491")
      (value ".1u 50V")
      (footprint "eagle-import:C0603K")
      (libsource (lib "eagle-import") (part "C-USC0603K"))
    )
    (comp (ref "C492")
      (value ".1u 50V")
      (footprint "eagle-import:C0603K")
      (libsource (lib "eagle-import") (part "C-USC0603K"))
    )
    (comp (ref "C493")
      (value ".1u 50V")
      (footprint "eagle-import:C0603K")
      (libsource (lib "eagle-import") (part "C-USC0603K"))
    )
    (comp (ref "C500")
      (value "NFM41PC155B1E3")
      (footprint "eagle-import:NFM1806")
      (libsource (lib "eagle-import") (part "NFM41PC155B1E3"))
    )
    (comp (ref "IC1")
      (value "SCA-4-10+")
      (footprint "eagle-import:SCA-4-10+")
      (libsource (lib "eagle-import") (part "SCA-4-10+"))
    )
    (comp (ref "IC58")
      (value "LMZ31707RVQ")
      (footprint "eagle-import:RVQ")
      (libsource (lib "eagle-import") (part "LMZ31707RVQ"))
    )
    (comp (ref "J1")
      (value "22-27-2021-02")
      (footprint "eagle-import:6410-02")
      (libsource (lib "eagle-import") (part "22-?-0227-2021"))
    )
    (comp (ref "L31")
      (value "BLM31PG121SN1L")
      (footprint "eagle-import:1206")
      (libsource (lib "eagle-import") (part "WE-CBF_1206"))
    )
    (comp (ref "LED1")
      (value "LTST-C170GKT")
      (footprint "eagle-import:CHIPLED_0805")
      (libsource (lib "eagle-import") (part "LEDCHIPLED_0805"))
    )
    (comp (ref "R1")
      (value "14k")
      (footprint "eagle-import:R0603")
      (libsource (lib "eagle-import") (part "R-US_R0603"))
    )
    (comp (ref "R4")
      (value "68.1k")
      (footprint "eagle-import:R0603")
      (libsource (lib "eagle-import") (part "R-US_R0603"))
    )
    (comp (ref "R201")
      (value "560")
      (footprint "eagle-import:R0603")
      (libsource (lib "eagle-import") (part "R-US_R0603"))
    )
    (comp (ref "R205")
      (value "182")
      (footprint "eagle-import:R0603")
      (libsource (lib "eagle-import") (part "R-US_R0603"))
    )
    (comp (ref "R206")
      (value "53.6k")
      (footprint "eagle-import:R0603")
      (libsource (lib "eagle-import") (part "R-US_R0603"))
    )
    (comp (ref "TP10")
      (value "TPSQB1,27")
      (footprint "eagle-import:B1,27")
      (libsource (lib "eagle-import") (part "TPSQB1,27"))
    )
    (comp (ref "X33")
      (value "0733660061")
      (footprint "eagle-import:BU-SMA-V")
      (libsource (lib "eagle-import") (part "BU-SMA-V"))
    )
    (comp (ref "C1")
      (value "100p")
      (footprint "eagle-import:C0603K")
      (libsource (lib "eagle-import") (part "C-USC0603K"))
    )
    (comp (ref "C2")
      (value "0.1u")
      (footprint "eagle-import:C0603K")
      (libsource (lib "eagle-import") (part "C-USC0603K"))
    )
    (comp (ref "C3")
      (value "100p")
      (footprint "eagle-import:C0603K")
      (libsource (lib "eagle-import") (part "C-USC0603K"))
    )
    (comp (ref "C4")
      (value "8p")
      (footprint "eagle-import:C0603K")
      (libsource (lib "eagle-import") (part "C-USC0603K"))
    )
    (comp (ref "C5")
      (value "12p")
      (footprint "eagle-import:C0603K")
      (libsource (lib "eagle-import") (part "C-USC0603K"))
    )
    (comp (ref "C6")
      (value "0.1u")
      (footprint "eagle-import:C0603K")
      (libsource (lib "eagle-import") (part "C-USC0603K"))
    )
    (comp (ref "C7")
      (value "100p")
      (footprint "eagle-import:C0603K")
      (libsource (lib "eagle-import") (part "C-USC0603K"))
    )
    (comp (ref "C8")
      (value "8p")
      (footprint "eagle-import:C0603K")
      (libsource (lib "eagle-import") (part "C-USC0603K"))
    )
    (comp (ref "C9")
      (value "12p")
      (footprint "eagle-import:C0603K")
      (libsource (lib "eagle-import") (part "C-USC0603K"))
    )
    (comp (ref "C10")
      (value "0.1u")
      (footprint "eagle-import:C0603K")
      (libsource (lib "eagle-import") (part "C-USC0603K"))
    )
    (comp (ref "C11")
      (value "100p")
      (footprint "eagle-import:C0603K")
      (libsource (lib "eagle-import") (part "C-USC0603K"))
    )
    (comp (ref "C12")
      (value "8p")
      (footprint "eagle-import:C0603K")
      (libsource (lib "eagle-import") (part "C-USC0603K"))
    )
    (comp (ref "C13")
      (value "12p")
      (footprint "eagle-import:C0603K")
      (libsource (lib "eagle-import") (part "C-USC0603K"))
    )
    (comp (ref "C53")
      (value "470n")
      (footprint "eagle-import:C0603K")
      (libsource (lib "eagle-import") (part "C-USC0603K"))
    )
    (comp (ref "C54")
      (value "470n")
      (footprint "eagle-import:C0603K")
      (libsource (lib "eagle-import") (part "C-USC0603K"))
    )
    (comp (ref "C55")
      (value "NFM21PS106B0J3D")
      (footprint "eagle-import:NFM21PS")
      (libsource (lib "eagle-import") (part "NFM21PS"))
    )
    (comp (ref "C56")
      (value "NFM21PS106B0J3D")
      (footprint "eagle-import:NFM21PS")
      (libsource (lib "eagle-import") (part "NFM21PS"))
    )
    (comp (ref "C58")
      (value "470n")
      (footprint "eagle-import:C0603K")
      (libsource (lib "eagle-import") (part "C-USC0603K"))
    )
    (comp (ref "C59")
      (value "470n")
      (footprint "eagle-import:C0603K")
      (libsource (lib "eagle-import") (part "C-USC0603K"))
    )
    (comp (ref "C60")
      (value "NFM21PS106B0J3D")
      (footprint "eagle-import:NFM21PS")
      (libsource (lib "eagle-import") (part "NFM21PS"))
    )
    (comp (ref "C61")
      (value "NFM21PS106B0J3D")
      (footprint "eagle-import:NFM21PS")
      (libsource (lib "eagle-import") (part "NFM21PS"))
    )
    (comp (ref "C62")
      (value "470n")
      (footprint "eagle-import:C0603K")
      (libsource (lib "eagle-import") (part "C-USC0603K"))
    )
    (comp (ref "C63")
      (value "470n")
      (footprint "eagle-import:C0603K")
      (libsource (lib "eagle-import") (part "C-USC0603K"))
    )
    (comp (ref "C64")
      (value "NFM21PS106B0J3D")
      (footprint "eagle-import:NFM21PS")
      (libsource (lib "eagle-import") (part "NFM21PS"))
    )
    (comp (ref "C65")
      (value "NFM21PS106B0J3D")
      (footprint "eagle-import:NFM21PS")
      (libsource (lib "eagle-import") (part "NFM21PS"))
    )
    (comp (ref "L1")
      (value "100n")
      (footprint "eagle-import:C1206")
      (libsource (lib "eagle-import") (part "L-US1206"))
    )
    (comp (ref "L2")
      (value "56n")
      (footprint "eagle-import:C1206")
      (libsource (lib "eagle-import") (part "L-US1206"))
    )
    (comp (ref "L3")
      (value "47n")
      (footprint "eagle-import:C1206")
      (libsource (lib "eagle-import") (part "L-US1206"))
    )
    (comp (ref "L4")
      (value "100n")
      (footprint "eagle-import:C1206")
      (libsource (lib "eagle-import") (part "L-US1206"))
    )
    (comp (ref "L5")
      (value "56n")
      (footprint "eagle-import:C1206")
      (libsource (lib "eagle-import") (part "L-US1206"))
    )
    (comp (ref "L6")
      (value "47n")
      (footprint "eagle-import:C1206")
      (libsource (lib "eagle-import") (part "L-US1206"))
    )
    (comp (ref "L7")
      (value "100n")
      (footprint "eagle-import:C1206")
      (libsource (lib "eagle-import") (part "L-US1206"))
    )
    (comp (ref "L8")
      (value "56n")
      (footprint "eagle-import:C1206")
      (libsource (lib "eagle-import") (part "L-US1206"))
    )
    (comp (ref "L9")
      (value "47n")
      (footprint "eagle-import:C1206")
      (libsource (lib "eagle-import") (part "L-US1206"))
    )
    (comp (ref "LDO_1")
      (value "TPS7A8101DRB")
      (footprint "eagle-import:DRB")
      (libsource (lib "eagle-import") (part "TPS7A8101DRB"))
    )
    (comp (ref "LDO_2")
      (value "TPS7A8101DRB")
      (footprint "eagle-import:DRB")
      (libsource (lib "eagle-import") (part "TPS7A8101DRB"))
    )
    (comp (ref "LDO_3")
      (value "TPS7A8101DRB")
      (footprint "eagle-import:DRB")
      (libsource (lib "eagle-import") (part "TPS7A8101DRB"))
    )
    (comp (ref "LNA_1")
      (value "SPF-5043Z")
      (footprint "eagle-import:SPF-5043Z")
      (libsource (lib "eagle-import") (part "SPF-5043Z"))
    )
    (comp (ref "LNA_2")
      (value "SPF-5043Z")
      (footprint "eagle-import:SPF-5043Z")
      (libsource (lib "eagle-import") (part "SPF-5043Z"))
    )
    (comp (ref "LNA_3")
      (value "SPF-5043Z")
      (footprint "eagle-import:SPF-5043Z")
      (libsource (lib "eagle-import") (part "SPF-5043Z"))
    )
    (comp (ref "R2")
      (value "52.3k")
      (footprint "eagle-import:R0603")
      (libsource (lib "eagle-import") (part "R-US_R0603"))
    )
    (comp (ref "R3")
      (value "10.0k")
      (footprint "eagle-import:R0603")
      (libsource (lib "eagle-import") (part "R-US_R0603"))
    )
    (comp (ref "R6")
      (value "52.3k")
      (footprint "eagle-import:R0603")
      (libsource (lib "eagle-import") (part "R-US_R0603"))
    )
    (comp (ref "R7")
      (value "10.0k")
      (footprint "eagle-import:R0603")
      (libsource (lib "eagle-import") (part "R-US_R0603"))
    )
    (comp (ref "R9")
      (value "52.3k")
      (footprint "eagle-import:R0603")
      (libsource (lib "eagle-import") (part "R-US_R0603"))
    )
    (comp (ref "R10")
      (value "10.0k")
      (footprint "eagle-import:R0603")
      (libsource (lib "eagle-import") (part "R-US_R0603"))
    )
    (comp (ref "SAW_1")
      (value "SXBP-140+")
      (footprint "eagle-import:SXBP-140+")
      (libsource (lib "eagle-import") (part "SXBP-140+"))
    )
    (comp (ref "SAW_2")
      (value "TA147FD")
      (footprint "eagle-import:TA147FD")
      (libsource (lib "eagle-import") (part "TA147FD"))
    )
    (comp (ref "SAW_3")
      (value "TA147FD")
      (footprint "eagle-import:TA147FD")
      (libsource (lib "eagle-import") (part "TA147FD"))
    )
    (comp (ref "SAW_4")
      (value "TA147FD")
      (footprint "eagle-import:TA147FD")
      (libsource (lib "eagle-import") (part "TA147FD"))
    )
    (comp (ref "TP_1")
      (value "TPTP20SQ")
      (footprint "eagle-import:TP20SQ")
      (libsource (lib "eagle-import") (part "TPTP20SQ"))
    )
    (comp (ref "TP_2")
      (value "TPTP20SQ")
      (footprint "eagle-import:TP20SQ")
      (libsource (lib "eagle-import") (part "TPTP20SQ"))
    )
    (comp (ref "TP_3")
      (value "TPTP20SQ")
      (footprint "eagle-import:TP20SQ")
      (libsource (lib "eagle-import") (part "TPTP20SQ"))
    )
    (comp (ref "X1")
      (value "0733660061")
      (footprint "eagle-import:BU-SMA-V")
      (libsource (lib "eagle-import") (part "BU-SMA-V"))
    )
    (comp (ref "X2")
      (value "0733660061")
      (footprint "eagle-import:BU-SMA-V")
      (libsource (lib "eagle-import") (part "BU-SMA-V"))
    )
    (comp (ref "X3")
      (value "0733660061")
      (footprint "eagle-import:BU-SMA-V")
      (libsource (lib "eagle-import") (part "BU-SMA-V"))
    )
    (comp (ref "X4")
      (value "0733660061")
      (footprint "eagle-import:BU-SMA-V")
      (libsource (lib "eagle-import") (part "BU-SMA-V"))
    )
    (comp (ref "X5")
      (value "0733660061")
      (footprint "eagle-import:BU-SMA-V")
      (libsource (lib "eagle-import") (part "BU-SMA-V"))
    )
    (comp (ref "X6")
      (value "0733660061")
      (footprint "eagle-import:BU-SMA-V")
      (libsource (lib "eagle-import") (part "BU-SMA-V"))
    )
    (comp (ref "X7")
      (value "0733660061")
      (footprint "eagle-import:BU-SMA-V")
      (libsource (lib "eagle-import") (part "BU-SMA-V"))
    )
    (comp (ref "X8")
      (value "0733660061")
      (footprint "eagle-import:BU-SMA-V")
      (libsource (lib "eagle-import") (part "BU-SMA-V"))
    )
    (comp (ref "C26")
      (value "100p")
      (footprint "eagle-import:C0603K")
      (libsource (lib "eagle-import") (part "C-USC0603K"))
    )
    (comp (ref "C27")
      (value "0.1u")
      (footprint "eagle-import:C0603K")
      (libsource (lib "eagle-import") (part "C-USC0603K"))
    )
    (comp (ref "C28")
      (value "100p")
      (footprint "eagle-import:C0603K")
      (libsource (lib "eagle-import") (part "C-USC0603K"))
    )
    (comp (ref "C29")
      (value "100p")
      (footprint "eagle-import:C0603K")
      (libsource (lib "eagle-import") (part "C-USC0603K"))
    )
    (comp (ref "C30")
      (value "100p")
      (footprint "eagle-import:C0603K")
      (libsource (lib "eagle-import") (part "C-USC0603K"))
    )
    (comp (ref "C31")
      (value "0.1u")
      (footprint "eagle-import:C0603K")
      (libsource (lib "eagle-import") (part "C-USC0603K"))
    )
    (comp (ref "C32")
      (value "100p")
      (footprint "eagle-import:C0603K")
      (libsource (lib "eagle-import") (part "C-USC0603K"))
    )
    (comp (ref "C33")
      (value "100p")
      (footprint "eagle-import:C0603K")
      (libsource (lib "eagle-import") (part "C-USC0603K"))
    )
    (comp (ref "C34")
      (value "100p")
      (footprint "eagle-import:C0603K")
      (libsource (lib "eagle-import") (part "C-USC0603K"))
    )
    (comp (ref "C35")
      (value "0.1u")
      (footprint "eagle-import:C0603K")
      (libsource (lib "eagle-import") (part "C-USC0603K"))
    )
    (comp (ref "C36")
      (value "100p")
      (footprint "eagle-import:C0603K")
      (libsource (lib "eagle-import") (part "C-USC0603K"))
    )
    (comp (ref "C37")
      (value "100p")
      (footprint "eagle-import:C0603K")
      (libsource (lib "eagle-import") (part "C-USC0603K"))
    )
    (comp (ref "C80")
      (value "470n")
      (footprint "eagle-import:C0603K")
      (libsource (lib "eagle-import") (part "C-USC0603K"))
    )
    (comp (ref "C81")
      (value "470n")
      (footprint "eagle-import:C0603K")
      (libsource (lib "eagle-import") (part "C-USC0603K"))
    )
    (comp (ref "C82")
      (value "NFM21PS106B0J3D")
      (footprint "eagle-import:NFM21PS")
      (libsource (lib "eagle-import") (part "NFM21PS"))
    )
    (comp (ref "C83")
      (value "NFM21PS106B0J3D")
      (footprint "eagle-import:NFM21PS")
      (libsource (lib "eagle-import") (part "NFM21PS"))
    )
    (comp (ref "C84")
      (value "470n")
      (footprint "eagle-import:C0603K")
      (libsource (lib "eagle-import") (part "C-USC0603K"))
    )
    (comp (ref "C85")
      (value "470n")
      (footprint "eagle-import:C0603K")
      (libsource (lib "eagle-import") (part "C-USC0603K"))
    )
    (comp (ref "C86")
      (value "NFM21PS106B0J3D")
      (footprint "eagle-import:NFM21PS")
      (libsource (lib "eagle-import") (part "NFM21PS"))
    )
    (comp (ref "C87")
      (value "NFM21PS106B0J3D")
      (footprint "eagle-import:NFM21PS")
      (libsource (lib "eagle-import") (part "NFM21PS"))
    )
    (comp (ref "C88")
      (value "470n")
      (footprint "eagle-import:C0603K")
      (libsource (lib "eagle-import") (part "C-USC0603K"))
    )
    (comp (ref "C89")
      (value "470n")
      (footprint "eagle-import:C0603K")
      (libsource (lib "eagle-import") (part "C-USC0603K"))
    )
    (comp (ref "C90")
      (value "NFM21PS106B0J3D")
      (footprint "eagle-import:NFM21PS")
      (libsource (lib "eagle-import") (part "NFM21PS"))
    )
    (comp (ref "C91")
      (value "NFM21PS106B0J3D")
      (footprint "eagle-import:NFM21PS")
      (libsource (lib "eagle-import") (part "NFM21PS"))
    )
    (comp (ref "L13")
      (value "100n")
      (footprint "eagle-import:C1206")
      (libsource (lib "eagle-import") (part "L-US1206"))
    )
    (comp (ref "L14")
      (value "100n")
      (footprint "eagle-import:C1206")
      (libsource (lib "eagle-import") (part "L-US1206"))
    )
    (comp (ref "L15")
      (value "100n")
      (footprint "eagle-import:C1206")
      (libsource (lib "eagle-import") (part "L-US1206"))
    )
    (comp (ref "LDO_7")
      (value "TPS7A8101DRB")
      (footprint "eagle-import:DRB")
      (libsource (lib "eagle-import") (part "TPS7A8101DRB"))
    )
    (comp (ref "LDO_8")
      (value "TPS7A8101DRB")
      (footprint "eagle-import:DRB")
      (libsource (lib "eagle-import") (part "TPS7A8101DRB"))
    )
    (comp (ref "LDO_9")
      (value "TPS7A8101DRB")
      (footprint "eagle-import:DRB")
      (libsource (lib "eagle-import") (part "TPS7A8101DRB"))
    )
    (comp (ref "LNA_7")
      (value "SPF-5043Z")
      (footprint "eagle-import:SPF-5043Z")
      (libsource (lib "eagle-import") (part "SPF-5043Z"))
    )
    (comp (ref "LNA_8")
      (value "SPF-5043Z")
      (footprint "eagle-import:SPF-5043Z")
      (libsource (lib "eagle-import") (part "SPF-5043Z"))
    )
    (comp (ref "LNA_9")
      (value "SPF-5043Z")
      (footprint "eagle-import:SPF-5043Z")
      (libsource (lib "eagle-import") (part "SPF-5043Z"))
    )
    (comp (ref "R25")
      (value "52.3k")
      (footprint "eagle-import:R0603")
      (libsource (lib "eagle-import") (part "R-US_R0603"))
    )
    (comp (ref "R26")
      (value "10.0k")
      (footprint "eagle-import:R0603")
      (libsource (lib "eagle-import") (part "R-US_R0603"))
    )
    (comp (ref "R28")
      (value "52.3k")
      (footprint "eagle-import:R0603")
      (libsource (lib "eagle-import") (part "R-US_R0603"))
    )
    (comp (ref "R29")
      (value "10.0k")
      (footprint "eagle-import:R0603")
      (libsource (lib "eagle-import") (part "R-US_R0603"))
    )
    (comp (ref "R31")
      (value "52.3k")
      (footprint "eagle-import:R0603")
      (libsource (lib "eagle-import") (part "R-US_R0603"))
    )
    (comp (ref "R32")
      (value "10.0k")
      (footprint "eagle-import:R0603")
      (libsource (lib "eagle-import") (part "R-US_R0603"))
    )
    (comp (ref "SAW_9")
      (value "TA1914A")
      (footprint "eagle-import:TA1914A")
      (libsource (lib "eagle-import") (part "TA1914A"))
    )
    (comp (ref "SAW_10")
      (value "TA1914A")
      (footprint "eagle-import:TA1914A")
      (libsource (lib "eagle-import") (part "TA1914A"))
    )
    (comp (ref "SAW_11")
      (value "TA1914A")
      (footprint "eagle-import:TA1914A")
      (libsource (lib "eagle-import") (part "TA1914A"))
    )
    (comp (ref "SAW_12")
      (value "TA1914A")
      (footprint "eagle-import:TA1914A")
      (libsource (lib "eagle-import") (part "TA1914A"))
    )
    (comp (ref "TP_7")
      (value "TPTP20SQ")
      (footprint "eagle-import:TP20SQ")
      (libsource (lib "eagle-import") (part "TPTP20SQ"))
    )
    (comp (ref "TP_8")
      (value "TPTP20SQ")
      (footprint "eagle-import:TP20SQ")
      (libsource (lib "eagle-import") (part "TPTP20SQ"))
    )
    (comp (ref "TP_9")
      (value "TPTP20SQ")
      (footprint "eagle-import:TP20SQ")
      (libsource (lib "eagle-import") (part "TPTP20SQ"))
    )
    (comp (ref "X17")
      (value "0733660061")
      (footprint "eagle-import:BU-SMA-V")
      (libsource (lib "eagle-import") (part "BU-SMA-V"))
    )
    (comp (ref "X18")
      (value "0733660061")
      (footprint "eagle-import:BU-SMA-V")
      (libsource (lib "eagle-import") (part "BU-SMA-V"))
    )
    (comp (ref "X19")
      (value "0733660061")
      (footprint "eagle-import:BU-SMA-V")
      (libsource (lib "eagle-import") (part "BU-SMA-V"))
    )
    (comp (ref "X20")
      (value "0733660061")
      (footprint "eagle-import:BU-SMA-V")
      (libsource (lib "eagle-import") (part "BU-SMA-V"))
    )
    (comp (ref "X21")
      (value "0733660061")
      (footprint "eagle-import:BU-SMA-V")
      (libsource (lib "eagle-import") (part "BU-SMA-V"))
    )
    (comp (ref "X22")
      (value "0733660061")
      (footprint "eagle-import:BU-SMA-V")
      (libsource (lib "eagle-import") (part "BU-SMA-V"))
    )
    (comp (ref "X23")
      (value "0733660061")
      (footprint "eagle-import:BU-SMA-V")
      (libsource (lib "eagle-import") (part "BU-SMA-V"))
    )
    (comp (ref "X24")
      (value "0733660061")
      (footprint "eagle-import:BU-SMA-V")
      (libsource (lib "eagle-import") (part "BU-SMA-V"))
    )
  )
  (nets
    (net (code "1") (name "+5V3") (class "Default")
      (node (ref "C459") (pin "OUT") (pinfunction "OUT_OUT") (pintype "bidirectional"))
      (node (ref "C55") (pin "IN") (pinfunction "IN_IN") (pintype "bidirectional"))
      (node (ref "C60") (pin "IN") (pinfunction "IN_IN") (pintype "bidirectional"))
      (node (ref "C64") (pin "IN") (pinfunction "IN_IN") (pintype "bidirectional"))
      (node (ref "C68") (pin "IN") (pinfunction "IN_IN") (pintype "bidirectional"))
      (node (ref "C74") (pin "IN") (pinfunction "IN_IN") (pintype "bidirectional"))
      (node (ref "C78") (pin "IN") (pinfunction "IN_IN") (pintype "bidirectional"))
      (node (ref "C82") (pin "IN") (pinfunction "IN_IN") (pintype "bidirectional"))
      (node (ref "C86") (pin "IN") (pinfunction "IN_IN") (pintype "bidirectional"))
      (node (ref "C90") (pin "IN") (pinfunction "IN_IN") (pintype "bidirectional"))
      (node (ref "C94") (pin "IN") (pinfunction "IN_IN") (pintype "bidirectional"))
      (node (ref "C98") (pin "IN") (pinfunction "IN_IN") (pintype "bidirectional"))
      (node (ref "IC58") (pin "27") (pinfunction "SENSE+_27") (pintype "bidirectional"))
      (node (ref "LDO_1") (pin "5") (pinfunction "EN_5") (pintype "bidirectional"))
      (node (ref "LDO_10") (pin "5") (pinfunction "EN_5") (pintype "bidirectional"))
      (node (ref "LDO_11") (pin "5") (pinfunction "EN_5") (pintype "bidirectional"))
      (node (ref "LDO_2") (pin "5") (pinfunction "EN_5") (pintype "bidirectional"))
      (node (ref "LDO_3") (pin "5") (pinfunction "EN_5") (pintype "bidirectional"))
      (node (ref "LDO_4") (pin "5") (pinfunction "EN_5") (pintype "bidirectional"))
      (node (ref "LDO_5") (pin "5") (pinfunction "EN_5") (pintype "bidirectional"))
      (node (ref "LDO_6") (pin "5") (pinfunction "EN_5") (pintype "bidirectional"))
      (node (ref "LDO_7") (pin "5") (pinfunction "EN_5") (pintype "bidirectional"))
      (node (ref "LDO_8") (pin "5") (pinfunction "EN_5") (pintype "bidirectional"))
      (node (ref "LDO_9") (pin "5") (pinfunction "EN_5") (pintype "bidirectional"))
      (node (ref "R201") (pin "2") (pinfunction "2_2") (pintype "passive"))
    )
    (net (code "2") (name "1.25_RF_OUT") (class "Default")
      (node (ref "IC1") (pin "7") (pinfunction "PORT_2_7") (pintype "bidirectional"))
      (node (ref "SAW_8") (pin "6") (pinfunction "OUTPUT_6") (pintype "bidirectional"))
      (node (ref "X16") (pin "1") (pinfunction "1_1") (pintype "passive"))
    )
    (net (code "3") (name "2M_RF_OUT") (class "Default")
      (node (ref "C13") (pin "2") (pinfunction "2_2") (pintype "passive"))
      (node (ref "IC1") (pin "9") (pinfunction "PORT_3_9") (pintype "bidirectional"))
      (node (ref "X8") (pin "1") (pinfunction "1_1") (pintype "passive"))
    )
    (net (code "4") (name "4M_RF_OUT") (class "Default")
      (node (ref "IC1") (pin "10") (pinfunction "PORT_4_10") (pintype "bidirectional"))
      (node (ref "L33") (pin "2") (pinfunction "2_2") (pintype "passive"))
      (node (ref "R17") (pin "2") (pinfunction "2_2") (pintype "passive"))
      (node (ref "X30") (pin "1") (pinfunction "1_1") (pintype "passive"))
    )
    (net (code "5") (name "70CM_RF_OUT") (class "Default")
      (node (ref "IC1") (pin "6") (pinfunction "PORT_1_6") (pintype "bidirectional"))
      (node (ref "SAW_12") (pin "5") (pinfunction "OUTPUT_5") (pintype "bidirectional"))
      (node (ref "X24") (pin "1") (pinfunction "1_1") (pintype "passive"))
    )
    (net (code "6") (name "GND") (class "Default")
      (node (ref "C10") (pin "2") (pinfunction "2_2") (pintype "passive"))
      (node (ref "C100") (pin "2") (pinfunction "2_2") (pintype "passive"))
      (node (ref "C102") (pin "2") (pinfunction "2_2") (pintype "passive"))
      (node (ref "C103") (pin "2") (pinfunction "2_2") (pintype "passive"))
      (node (ref "C105") (pin "2") (pinfunction "2_2") (pintype "passive"))
      (node (ref "C107") (pin "2") (pinfunction "2_2") (pintype "passive"))
      (node (ref "C108") (pin "2") (pinfunction "2_2") (pintype "passive"))
      (node (ref "C11") (pin "2") (pinfunction "2_2") (pintype "passive"))
      (node (ref "C15") (pin "2") (pinfunction "2_2") (pintype "passive"))
      (node (ref "C16") (pin "2") (pinfunction "2_2") (pintype "passive"))
      (node (ref "C19") (pin "2") (pinfunction "2_2") (pintype "passive"))
      (node (ref "C2") (pin "2") (pinfunction "2_2") (pintype "passive"))
      (node (ref "C20") (pin "2") (pinfunction "2_2") (pintype "passive"))
      (node (ref "C23") (pin "2") (pinfunction "2_2") (pintype "passive"))
      (node (ref "C24") (pin "2") (pinfunction "2_2") (pintype "passive"))
      (node (ref "C27") (pin "2") (pinfunction "2_2") (pintype "passive"))
      (node (ref "C28") (pin "2") (pinfunction "2_2") (pintype "passive"))
      (node (ref "C3") (pin "2") (pinfunction "2_2") (pintype "passive"))
      (node (ref "C31") (pin "2") (pinfunction "2_2") (pintype "passive"))
      (node (ref "C32") (pin "2") (pinfunction "2_2") (pintype "passive"))
      (node (ref "C35") (pin "2") (pinfunction "2_2") (pintype "passive"))
      (node (ref "C36") (pin "2") (pinfunction "2_2") (pintype "passive"))
      (node (ref "C39") (pin "2") (pinfunction "2_2") (pintype "passive"))
      (node (ref "C40") (pin "2") (pinfunction "2_2") (pintype "passive"))
      (node (ref "C41") (pin "2") (pinfunction "2_2") (pintype "passive"))
      (node (ref "C44") (pin "2") (pinfunction "2_2") (pintype "passive"))
      (node (ref "C45") (pin "2") (pinfunction "2_2") (pintype "passive"))
      (node (ref "C459") (pin "GND1") (pinfunction "GND_GND1") (pintype "bidirectional"))
      (node (ref "C459") (pin "GND2") (pinfunction "GND_GND2") (pintype "bidirectional"))
      (node (ref "C459") (pin "GND3") (pinfunction "GND_GND3") (pintype "bidirectional"))
      (node (ref "C459") (pin "GND4") (pinfunction "GND_GND4") (pintype "bidirectional"))
      (node (ref "C459") (pin "GND5") (pinfunction "GND_GND5") (pintype "bidirectional"))
      (node (ref "C46") (pin "2") (pinfunction "2_2") (pintype "passive"))
      (node (ref "C48") (pin "2") (pinfunction "2_2") (pintype "passive"))
      (node (ref "C481") (pin "2") (pinfunction "2_2") (pintype "passive"))
      (node (ref "C482") (pin "2") (pinfunction "2_2") (pintype "passive"))
      (node (ref "C483") (pin "-") (pinfunction "-_-") (pintype "passive"))
      (node (ref "C484") (pin "-") (pinfunction "-_-") (pintype "passive"))
      (node (ref "C489") (pin "2") (pinfunction "2_2") (pintype "passive"))
      (node (ref "C490") (pin "2") (pinfunction "2_2") (pintype "passive"))
      (node (ref "C491") (pin "2") (pinfunction "2_2") (pintype "passive"))
      (node (ref "C492") (pin "2") (pinfunction "2_2") (pintype "passive"))
      (node (ref "C493") (pin "2") (pinfunction "2_2") (pintype "passive"))
      (node (ref "C500") (pin "GND@1") (pinfunction "GND_GND@1") (pintype "power_in"))
      (node (ref "C500") (pin "GND@2") (pinfunction "GND_GND@2") (pintype "power_in"))
      (node (ref "C51") (pin "2") (pinfunction "2_2") (pintype "passive"))
      (node (ref "C52") (pin "2") (pinfunction "2_2") (pintype "passive"))
      (node (ref "C53") (pin "2") (pinfunction "2_2") (pintype "passive"))
      (node (ref "C55") (pin "GND1") (pinfunction "GND_GND1") (pintype "bidirectional"))
      (node (ref "C55") (pin "GND2") (pinfunction "GND_GND2") (pintype "bidirectional"))
      (node (ref "C55") (pin "GND3") (pinfunction "GND_GND3") (pintype "bidirectional"))
      (node (ref "C55") (pin "GND4") (pinfunction "GND_GND4") (pintype "bidirectional"))
      (node (ref "C55") (pin "GND5") (pinfunction "GND_GND5") (pintype "bidirectional"))
      (node (ref "C55") (pin "GND6") (pinfunction "GND_GND6") (pintype "bidirectional"))
      (node (ref "C55") (pin "GND7") (pinfunction "GND_GND7") (pintype "bidirectional"))
      (node (ref "C55") (pin "GND8") (pinfunction "GND_GND8") (pintype "bidirectional"))
      (node (ref "C56") (pin "GND1") (pinfunction "GND_GND1") (pintype "bidirectional"))
      (node (ref "C56") (pin "GND2") (pinfunction "GND_GND2") (pintype "bidirectional"))
      (node (ref "C56") (pin "GND3") (pinfunction "GND_GND3") (pintype "bidirectional"))
      (node (ref "C56") (pin "GND4") (pinfunction "GND_GND4") (pintype "bidirectional"))
      (node (ref "C56") (pin "GND5") (pinfunction "GND_GND5") (pintype "bidirectional"))
      (node (ref "C56") (pin "GND6") (pinfunction "GND_GND6") (pintype "bidirectional"))
      (node (ref "C56") (pin "GND7") (pinfunction "GND_GND7") (pintype "bidirectional"))
      (node (ref "C56") (pin "GND8") (pinfunction "GND_GND8") (pintype "bidirectional"))
      (node (ref "C58") (pin "2") (pinfunction "2_2") (pintype "passive"))
      (node (ref "C6") (pin "2") (pinfunction "2_2") (pintype "passive"))
      (node (ref "C60") (pin "GND1") (pinfunction "GND_GND1") (pintype "bidirectional"))
      (node (ref "C60") (pin "GND2") (pinfunction "GND_GND2") (pintype "bidirectional"))
      (node (ref "C60") (pin "GND3") (pinfunction "GND_GND3") (pintype "bidirectional"))
      (node (ref "C60") (pin "GND4") (pinfunction "GND_GND4") (pintype "bidirectional"))
      (node (ref "C60") (pin "GND5") (pinfunction "GND_GND5") (pintype "bidirectional"))
      (node (ref "C60") (pin "GND6") (pinfunction "GND_GND6") (pintype "bidirectional"))
      (node (ref "C60") (pin "GND7") (pinfunction "GND_GND7") (pintype "bidirectional"))
      (node (ref "C60") (pin "GND8") (pinfunction "GND_GND8") (pintype "bidirectional"))
      (node (ref "C61") (pin "GND1") (pinfunction "GND_GND1") (pintype "bidirectional"))
      (node (ref "C61") (pin "GND2") (pinfunction "GND_GND2") (pintype "bidirectional"))
      (node (ref "C61") (pin "GND3") (pinfunction "GND_GND3") (pintype "bidirectional"))
      (node (ref "C61") (pin "GND4") (pinfunction "GND_GND4") (pintype "bidirectional"))
      (node (ref "C61") (pin "GND5") (pinfunction "GND_GND5") (pintype "bidirectional"))
      (node (ref "C61") (pin "GND6") (pinfunction "GND_GND6") (pintype "bidirectional"))
      (node (ref "C61") (pin "GND7") (pinfunction "GND_GND7") (pintype "bidirectional"))
      (node (ref "C61") (pin "GND8") (pinfunction "GND_GND8") (pintype "bidirectional"))
      (node (ref "C62") (pin "2") (pinfunction "2_2") (pintype "passive"))
      (node (ref "C64") (pin "GND1") (pinfunction "GND_GND1") (pintype "bidirectional"))
      (node (ref "C64") (pin "GND2") (pinfunction "GND_GND2") (pintype "bidirectional"))
      (node (ref "C64") (pin "GND3") (pinfunction "GND_GND3") (pintype "bidirectional"))
      (node (ref "C64") (pin "GND4") (pinfunction "GND_GND4") (pintype "bidirectional"))
      (node (ref "C64") (pin "GND5") (pinfunction "GND_GND5") (pintype "bidirectional"))
      (node (ref "C64") (pin "GND6") (pinfunction "GND_GND6") (pintype "bidirectional"))
      (node (ref "C64") (pin "GND7") (pinfunction "GND_GND7") (pintype "bidirectional"))
      (node (ref "C64") (pin "GND8") (pinfunction "GND_GND8") (pintype "bidirectional"))
      (node (ref "C65") (pin "GND1") (pinfunction "GND_GND1") (pintype "bidirectional"))
      (node (ref "C65") (pin "GND2") (pinfunction "GND_GND2") (pintype "bidirectional"))
      (node (ref "C65") (pin "GND3") (pinfunction "GND_GND3") (pintype "bidirectional"))
      (node (ref "C65") (pin "GND4") (pinfunction "GND_GND4") (pintype "bidirectional"))
      (node (ref "C65") (pin "GND5") (pinfunction "GND_GND5") (pintype "bidirectional"))
      (node (ref "C65") (pin "GND6") (pinfunction "GND_GND6") (pintype "bidirectional"))
      (node (ref "C65") (pin "GND7") (pinfunction "GND_GND7") (pintype "bidirectional"))
      (node (ref "C65") (pin "GND8") (pinfunction "GND_GND8") (pintype "bidirectional"))
      (node (ref "C66") (pin "2") (pinfunction "2_2") (pintype "passive"))
      (node (ref "C68") (pin "GND1") (pinfunction "GND_GND1") (pintype "bidirectional"))
      (node (ref "C68") (pin "GND2") (pinfunction "GND_GND2") (pintype "bidirectional"))
      (node (ref "C68") (pin "GND3") (pinfunction "GND_GND3") (pintype "bidirectional"))
      (node (ref "C68") (pin "GND4") (pinfunction "GND_GND4") (pintype "bidirectional"))
      (node (ref "C68") (pin "GND5") (pinfunction "GND_GND5") (pintype "bidirectional"))
      (node (ref "C68") (pin "GND6") (pinfunction "GND_GND6") (pintype "bidirectional"))
      (node (ref "C68") (pin "GND7") (pinfunction "GND_GND7") (pintype "bidirectional"))
      (node (ref "C68") (pin "GND8") (pinfunction "GND_GND8") (pintype "bidirectional"))
      (node (ref "C69") (pin "GND1") (pinfunction "GND_GND1") (pintype "bidirectional"))
      (node (ref "C69") (pin "GND2") (pinfunction "GND_GND2") (pintype "bidirectional"))
      (node (ref "C69") (pin "GND3") (pinfunction "GND_GND3") (pintype "bidirectional"))
      (node (ref "C69") (pin "GND4") (pinfunction "GND_GND4") (pintype "bidirectional"))
      (node (ref "C69") (pin "GND5") (pinfunction "GND_GND5") (pintype "bidirectional"))
      (node (ref "C69") (pin "GND6") (pinfunction "GND_GND6") (pintype "bidirectional"))
      (node (ref "C69") (pin "GND7") (pinfunction "GND_GND7") (pintype "bidirectional"))
      (node (ref "C69") (pin "GND8") (pinfunction "GND_GND8") (pintype "bidirectional"))
      (node (ref "C7") (pin "2") (pinfunction "2_2") (pintype "passive"))
      (node (ref "C70") (pin "2") (pinfunction "2_2") (pintype "passive"))
      (node (ref "C73") (pin "2") (pinfunction "2_2") (pintype "passive"))
      (node (ref "C74") (pin "GND1") (pinfunction "GND_GND1") (pintype "bidirectional"))
      (node (ref "C74") (pin "GND2") (pinfunction "GND_GND2") (pintype "bidirectional"))
      (node (ref "C74") (pin "GND3") (pinfunction "GND_GND3") (pintype "bidirectional"))
      (node (ref "C74") (pin "GND4") (pinfunction "GND_GND4") (pintype "bidirectional"))
      (node (ref "C74") (pin "GND5") (pinfunction "GND_GND5") (pintype "bidirectional"))
      (node (ref "C74") (pin "GND6") (pinfunction "GND_GND6") (pintype "bidirectional"))
      (node (ref "C74") (pin "GND7") (pinfunction "GND_GND7") (pintype "bidirectional"))
      (node (ref "C74") (pin "GND8") (pinfunction "GND_GND8") (pintype "bidirectional"))
      (node (ref "C75") (pin "GND1") (pinfunction "GND_GND1") (pintype "bidirectional"))
      (node (ref "C75") (pin "GND2") (pinfunction "GND_GND2") (pintype "bidirectional"))
      (node (ref "C75") (pin "GND3") (pinfunction "GND_GND3") (pintype "bidirectional"))
      (node (ref "C75") (pin "GND4") (pinfunction "GND_GND4") (pintype "bidirectional"))
      (node (ref "C75") (pin "GND5") (pinfunction "GND_GND5") (pintype "bidirectional"))
      (node (ref "C75") (pin "GND6") (pinfunction "GND_GND6") (pintype "bidirectional"))
      (node (ref "C75") (pin "GND7") (pinfunction "GND_GND7") (pintype "bidirectional"))
      (node (ref "C75") (pin "GND8") (pinfunction "GND_GND8") (pintype "bidirectional"))
      (node (ref "C76") (pin "2") (pinfunction "2_2") (pintype "passive"))
      (node (ref "C78") (pin "GND1") (pinfunction "GND_GND1") (pintype "bidirectional"))
      (node (ref "C78") (pin "GND2") (pinfunction "GND_GND2") (pintype "bidirectional"))
      (node (ref "C78") (pin "GND3") (pinfunction "GND_GND3") (pintype "bidirectional"))
      (node (ref "C78") (pin "GND4") (pinfunction "GND_GND4") (pintype "bidirectional"))
      (node (ref "C78") (pin "GND5") (pinfunction "GND_GND5") (pintype "bidirectional"))
      (node (ref "C78") (pin "GND6") (pinfunction "GND_GND6") (pintype "bidirectional"))
      (node (ref "C78") (pin "GND7") (pinfunction "GND_GND7") (pintype "bidirectional"))
      (node (ref "C78") (pin "GND8") (pinfunction "GND_GND8") (pintype "bidirectional"))
      (node (ref "C79") (pin "GND1") (pinfunction "GND_GND1") (pintype "bidirectional"))
      (node (ref "C79") (pin "GND2") (pinfunction "GND_GND2") (pintype "bidirectional"))
      (node (ref "C79") (pin "GND3") (pinfunction "GND_GND3") (pintype "bidirectional"))
      (node (ref "C79") (pin "GND4") (pinfunction "GND_GND4") (pintype "bidirectional"))
      (node (ref "C79") (pin "GND5") (pinfunction "GND_GND5") (pintype "bidirectional"))
      (node (ref "C79") (pin "GND6") (pinfunction "GND_GND6") (pintype "bidirectional"))
      (node (ref "C79") (pin "GND7") (pinfunction "GND_GND7") (pintype "bidirectional"))
      (node (ref "C79") (pin "GND8") (pinfunction "GND_GND8") (pintype "bidirectional"))
      (node (ref "C80") (pin "2") (pinfunction "2_2") (pintype "passive"))
      (node (ref "C82") (pin "GND1") (pinfunction "GND_GND1") (pintype "bidirectional"))
      (node (ref "C82") (pin "GND2") (pinfunction "GND_GND2") (pintype "bidirectional"))
      (node (ref "C82") (pin "GND3") (pinfunction "GND_GND3") (pintype "bidirectional"))
      (node (ref "C82") (pin "GND4") (pinfunction "GND_GND4") (pintype "bidirectional"))
      (node (ref "C82") (pin "GND5") (pinfunction "GND_GND5") (pintype "bidirectional"))
      (node (ref "C82") (pin "GND6") (pinfunction "GND_GND6") (pintype "bidirectional"))
      (node (ref "C82") (pin "GND7") (pinfunction "GND_GND7") (pintype "bidirectional"))
      (node (ref "C82") (pin "GND8") (pinfunction "GND_GND8") (pintype "bidirectional"))
      (node (ref "C83") (pin "GND1") (pinfunction "GND_GND1") (pintype "bidirectional"))
      (node (ref "C83") (pin "GND2") (pinfunction "GND_GND2") (pintype "bidirectional"))
      (node (ref "C83") (pin "GND3") (pinfunction "GND_GND3") (pintype "bidirectional"))
      (node (ref "C83") (pin "GND4") (pinfunction "GND_GND4") (pintype "bidirectional"))
      (node (ref "C83") (pin "GND5") (pinfunction "GND_GND5") (pintype "bidirectional"))
      (node (ref "C83") (pin "GND6") (pinfunction "GND_GND6") (pintype "bidirectional"))
      (node (ref "C83") (pin "GND7") (pinfunction "GND_GND7") (pintype "bidirectional"))
      (node (ref "C83") (pin "GND8") (pinfunction "GND_GND8") (pintype "bidirectional"))
      (node (ref "C84") (pin "2") (pinfunction "2_2") (pintype "passive"))
      (node (ref "C86") (pin "GND1") (pinfunction "GND_GND1") (pintype "bidirectional"))
      (node (ref "C86") (pin "GND2") (pinfunction "GND_GND2") (pintype "bidirectional"))
      (node (ref "C86") (pin "GND3") (pinfunction "GND_GND3") (pintype "bidirectional"))
      (node (ref "C86") (pin "GND4") (pinfunction "GND_GND4") (pintype "bidirectional"))
      (node (ref "C86") (pin "GND5") (pinfunction "GND_GND5") (pintype "bidirectional"))
      (node (ref "C86") (pin "GND6") (pinfunction "GND_GND6") (pintype "bidirectional"))
      (node (ref "C86") (pin "GND7") (pinfunction "GND_GND7") (pintype "bidirectional"))
      (node (ref "C86") (pin "GND8") (pinfunction "GND_GND8") (pintype "bidirectional"))
      (node (ref "C87") (pin "GND1") (pinfunction "GND_GND1") (pintype "bidirectional"))
      (node (ref "C87") (pin "GND2") (pinfunction "GND_GND2") (pintype "bidirectional"))
      (node (ref "C87") (pin "GND3") (pinfunction "GND_GND3") (pintype "bidirectional"))
      (node (ref "C87") (pin "GND4") (pinfunction "GND_GND4") (pintype "bidirectional"))
      (node (ref "C87") (pin "GND5") (pinfunction "GND_GND5") (pintype "bidirectional"))
      (node (ref "C87") (pin "GND6") (pinfunction "GND_GND6") (pintype "bidirectional"))
      (node (ref "C87") (pin "GND7") (pinfunction "GND_GND7") (pintype "bidirectional"))
      (node (ref "C87") (pin "GND8") (pinfunction "GND_GND8") (pintype "bidirectional"))
      (node (ref "C88") (pin "2") (pinfunction "2_2") (pintype "passive"))
      (node (ref "C90") (pin "GND1") (pinfunction "GND_GND1") (pintype "bidirectional"))
      (node (ref "C90") (pin "GND2") (pinfunction "GND_GND2") (pintype "bidirectional"))
      (node (ref "C90") (pin "GND3") (pinfunction "GND_GND3") (pintype "bidirectional"))
      (node (ref "C90") (pin "GND4") (pinfunction "GND_GND4") (pintype "bidirectional"))
      (node (ref "C90") (pin "GND5") (pinfunction "GND_GND5") (pintype "bidirectional"))
      (node (ref "C90") (pin "GND6") (pinfunction "GND_GND6") (pintype "bidirectional"))
      (node (ref "C90") (pin "GND7") (pinfunction "GND_GND7") (pintype "bidirectional"))
      (node (ref "C90") (pin "GND8") (pinfunction "GND_GND8") (pintype "bidirectional"))
      (node (ref "C91") (pin "GND1") (pinfunction "GND_GND1") (pintype "bidirectional"))
      (node (ref "C91") (pin "GND2") (pinfunction "GND_GND2") (pintype "bidirectional"))
      (node (ref "C91") (pin "GND3") (pinfunction "GND_GND3") (pintype "bidirectional"))
      (node (ref "C91") (pin "GND4") (pinfunction "GND_GND4") (pintype "bidirectional"))
      (node (ref "C91") (pin "GND5") (pinfunction "GND_GND5") (pintype "bidirectional"))
      (node (ref "C91") (pin "GND6") (pinfunction "GND_GND6") (pintype "bidirectional"))
      (node (ref "C91") (pin "GND7") (pinfunction "GND_GND7") (pintype "bidirectional"))
      (node (ref "C91") (pin "GND8") (pinfunction "GND_GND8") (pintype "bidirectional"))
      (node (ref "C92") (pin "2") (pinfunction "2_2") (pintype "passive"))
      (node (ref "C94") (pin "GND1") (pinfunction "GND_GND1") (pintype "bidirectional"))
      (node (ref "C94") (pin "GND2") (pinfunction "GND_GND2") (pintype "bidirectional"))
      (node (ref "C94") (pin "GND3") (pinfunction "GND_GND3") (pintype "bidirectional"))
      (node (ref "C94") (pin "GND4") (pinfunction "GND_GND4") (pintype "bidirectional"))
      (node (ref "C94") (pin "GND5") (pinfunction "GND_GND5") (pintype "bidirectional"))
      (node (ref "C94") (pin "GND6") (pinfunction "GND_GND6") (pintype "bidirectional"))
      (node (ref "C94") (pin "GND7") (pinfunction "GND_GND7") (pintype "bidirectional"))
      (node (ref "C94") (pin "GND8") (pinfunction "GND_GND8") (pintype "bidirectional"))
      (node (ref "C95") (pin "GND1") (pinfunction "GND_GND1") (pintype "bidirectional"))
      (node (ref "C95") (pin "GND2") (pinfunction "GND_GND2") (pintype "bidirectional"))
      (node (ref "C95") (pin "GND3") (pinfunction "GND_GND3") (pintype "bidirectional"))
      (node (ref "C95") (pin "GND4") (pinfunction "GND_GND4") (pintype "bidirectional"))
      (node (ref "C95") (pin "GND5") (pinfunction "GND_GND5") (pintype "bidirectional"))
      (node (ref "C95") (pin "GND6") (pinfunction "GND_GND6") (pintype "bidirectional"))
      (node (ref "C95") (pin "GND7") (pinfunction "GND_GND7") (pintype "bidirectional"))
      (node (ref "C95") (pin "GND8") (pinfunction "GND_GND8") (pintype "bidirectional"))
      (node (ref "C96") (pin "2") (pinfunction "2_2") (pintype "passive"))
      (node (ref "C98") (pin "GND1") (pinfunction "GND_GND1") (pintype "bidirectional"))
      (node (ref "C98") (pin "GND2") (pinfunction "GND_GND2") (pintype "bidirectional"))
      (node (ref "C98") (pin "GND3") (pinfunction "GND_GND3") (pintype "bidirectional"))
      (node (ref "C98") (pin "GND4") (pinfunction "GND_GND4") (pintype "bidirectional"))
      (node (ref "C98") (pin "GND5") (pinfunction "GND_GND5") (pintype "bidirectional"))
      (node (ref "C98") (pin "GND6") (pinfunction "GND_GND6") (pintype "bidirectional"))
      (node (ref "C98") (pin "GND7") (pinfunction "GND_GND7") (pintype "bidirectional"))
      (node (ref "C98") (pin "GND8") (pinfunction "GND_GND8") (pintype "bidirectional"))
      (node (ref "C99") (pin "GND1") (pinfunction "GND_GND1") (pintype "bidirectional"))
      (node (ref "C99") (pin "GND2") (pinfunction "GND_GND2") (pintype "bidirectional"))
      (node (ref "C99") (pin "GND3") (pinfunction "GND_GND3") (pintype "bidirectional"))
      (node (ref "C99") (pin "GND4") (pinfunction "GND_GND4") (pintype "bidirectional"))
      (node (ref "C99") (pin "GND5") (pinfunction "GND_GND5") (pintype "bidirectional"))
      (node (ref "C99") (pin "GND6") (pinfunction "GND_GND6") (pintype "bidirectional"))
      (node (ref "C99") (pin "GND7") (pinfunction "GND_GND7") (pintype "bidirectional"))
      (node (ref "C99") (pin "GND8") (pinfunction "GND_GND8") (pintype "bidirectional"))
      (node (ref "IC1") (pin "1") (pinfunction "GND_1_1") (pintype "bidirectional"))
      (node (ref "IC1") (pin "2") (pinfunction "GND_2_2") (pintype "bidirectional"))
      (node (ref "IC1") (pin "4") (pinfunction "GND_3_4") (pintype "bidirectional"))
      (node (ref "IC1") (pin "5") (pinfunction "GND_4_5") (pintype "bidirectional"))
      (node (ref "IC1") (pin "8") (pinfunction "GND_5_8") (pintype "bidirectional"))
      (node (ref "IC58") (pin "2") (pinfunction "AGND_2") (pintype "bidirectional"))
      (node (ref "IC58") (pin "20") (pinfunction "PGND_20") (pintype "bidirectional"))
      (node (ref "IC58") (pin "21") (pinfunction "PGND_21") (pintype "bidirectional"))
      (node (ref "IC58") (pin "23") (pinfunction "AGND_23") (pintype "bidirectional"))
      (node (ref "IC58") (pin "29") (pinfunction "STSEL_29") (pintype "bidirectional"))
      (node (ref "IC58") (pin "31") (pinfunction "PGND_31") (pintype "bidirectional"))
      (node (ref "IC58") (pin "32") (pinfunction "PGND_32") (pintype "bidirectional"))
      (node (ref "IC58") (pin "33") (pinfunction "PGND_33") (pintype "bidirectional"))
      (node (ref "J1") (pin "1") (pinfunction "S_1") (pintype "passive"))
      (node (ref "L17") (pin "1") (pinfunction "1_1") (pintype "passive"))
      (node (ref "L2") (pin "1") (pinfunction "1_1") (pintype "passive"))
      (node (ref "L22") (pin "1") (pinfunction "1_1") (pintype "passive"))
      (node (ref "L24") (pin "1") (pinfunction "1_1") (pintype "passive"))
      (node (ref "L26") (pin "1") (pinfunction "1_1") (pintype "passive"))
      (node (ref "L28") (pin "1") (pinfunction "1_1") (pintype "passive"))
      (node (ref "L3") (pin "1") (pinfunction "1_1") (pintype "passive"))
      (node (ref "L32") (pin "1") (pinfunction "1_1") (pintype "passive"))
      (node (ref "L5") (pin "1") (pinfunction "1_1") (pintype "passive"))
      (node (ref "L6") (pin "1") (pinfunction "1_1") (pintype "passive"))
      (node (ref "L8") (pin "1") (pinfunction "1_1") (pintype "passive"))
      (node (ref "L9") (pin "1") (pinfunction "1_1") (pintype "passive"))
      (node (ref "LDO_1") (pin "4") (pinfunction "GND_4") (pintype "bidirectional"))
      (node (ref "LDO_1") (pin "P1") (pinfunction "GND_P1") (pintype "bidirectional"))
      (node (ref "LDO_1") (pin "P2") (pinfunction "GND_P2") (pintype "bidirectional"))
      (node (ref "LDO_1") (pin "P3") (pinfunction "GND_P3") (pintype "bidirectional"))
      (node (ref "LDO_1") (pin "P4") (pinfunction "GND_P4") (pintype "bidirectional"))
      (node (ref "LDO_1") (pin "P5") (pinfunction "GND_P5") (pintype "bidirectional"))
      (node (ref "LDO_1") (pin "PAD") (pinfunction "GND_PAD") (pintype "bidirectional"))
      (node (ref "LDO_10") (pin "4") (pinfunction "GND_4") (pintype "bidirectional"))
      (node (ref "LDO_10") (pin "P1") (pinfunction "GND_P1") (pintype "bidirectional"))
      (node (ref "LDO_10") (pin "P2") (pinfunction "GND_P2") (pintype "bidirectional"))
      (node (ref "LDO_10") (pin "P3") (pinfunction "GND_P3") (pintype "bidirectional"))
      (node (ref "LDO_10") (pin "P4") (pinfunction "GND_P4") (pintype "bidirectional"))
      (node (ref "LDO_10") (pin "P5") (pinfunction "GND_P5") (pintype "bidirectional"))
      (node (ref "LDO_10") (pin "PAD") (pinfunction "GND_PAD") (pintype "bidirectional"))
      (node (ref "LDO_11") (pin "4") (pinfunction "GND_4") (pintype "bidirectional"))
      (node (ref "LDO_11") (pin "P1") (pinfunction "GND_P1") (pintype "bidirectional"))
      (node (ref "LDO_11") (pin "P2") (pinfunction "GND_P2") (pintype "bidirectional"))
      (node (ref "LDO_11") (pin "P3") (pinfunction "GND_P3") (pintype "bidirectional"))
      (node (ref "LDO_11") (pin "P4") (pinfunction "GND_P4") (pintype "bidirectional"))
      (node (ref "LDO_11") (pin "P5") (pinfunction "GND_P5") (pintype "bidirectional"))
      (node (ref "LDO_11") (pin "PAD") (pinfunction "GND_PAD") (pintype "bidirectional"))
      (node (ref "LDO_2") (pin "4") (pinfunction "GND_4") (pintype "bidirectional"))
      (node (ref "LDO_2") (pin "P1") (pinfunction "GND_P1") (pintype "bidirectional"))
      (node (ref "LDO_2") (pin "P2") (pinfunction "GND_P2") (pintype "bidirectional"))
      (node (ref "LDO_2") (pin "P3") (pinfunction "GND_P3") (pintype "bidirectional"))
      (node (ref "LDO_2") (pin "P4") (pinfunction "GND_P4") (pintype "bidirectional"))
      (node (ref "LDO_2") (pin "P5") (pinfunction "GND_P5") (pintype "bidirectional"))
      (node (ref "LDO_2") (pin "PAD") (pinfunction "GND_PAD") (pintype "bidirectional"))
      (node (ref "LDO_3") (pin "4") (pinfunction "GND_4") (pintype "bidirectional"))
      (node (ref "LDO_3") (pin "P1") (pinfunction "GND_P1") (pintype "bidirectional"))
      (node (ref "LDO_3") (pin "P2") (pinfunction "GND_P2") (pintype "bidirectional"))
      (node (ref "LDO_3") (pin "P3") (pinfunction "GND_P3") (pintype "bidirectional"))
      (node (ref "LDO_3") (pin "P4") (pinfunction "GND_P4") (pintype "bidirectional"))
      (node (ref "LDO_3") (pin "P5") (pinfunction "GND_P5") (pintype "bidirectional"))
      (node (ref "LDO_3") (pin "PAD") (pinfunction "GND_PAD") (pintype "bidirectional"))
      (node (ref "LDO_4") (pin "4") (pinfunction "GND_4") (pintype "bidirectional"))
      (node (ref "LDO_4") (pin "P1") (pinfunction "GND_P1") (pintype "bidirectional"))
      (node (ref "LDO_4") (pin "P2") (pinfunction "GND_P2") (pintype "bidirectional"))
      (node (ref "LDO_4") (pin "P3") (pinfunction "GND_P3") (pintype "bidirectional"))
      (node (ref "LDO_4") (pin "P4") (pinfunction "GND_P4") (pintype "bidirectional"))
      (node (ref "LDO_4") (pin "P5") (pinfunction "GND_P5") (pintype "bidirectional"))
      (node (ref "LDO_4") (pin "PAD") (pinfunction "GND_PAD") (pintype "bidirectional"))
      (node (ref "LDO_5") (pin "4") (pinfunction "GND_4") (pintype "bidirectional"))
      (node (ref "LDO_5") (pin "P1") (pinfunction "GND_P1") (pintype "bidirectional"))
      (node (ref "LDO_5") (pin "P2") (pinfunction "GND_P2") (pintype "bidirectional"))
      (node (ref "LDO_5") (pin "P3") (pinfunction "GND_P3") (pintype "bidirectional"))
      (node (ref "LDO_5") (pin "P4") (pinfunction "GND_P4") (pintype "bidirectional"))
      (node (ref "LDO_5") (pin "P5") (pinfunction "GND_P5") (pintype "bidirectional"))
      (node (ref "LDO_5") (pin "PAD") (pinfunction "GND_PAD") (pintype "bidirectional"))
      (node (ref "LDO_6") (pin "4") (pinfunction "GND_4") (pintype "bidirectional"))
      (node (ref "LDO_6") (pin "P1") (pinfunction "GND_P1") (pintype "bidirectional"))
      (node (ref "LDO_6") (pin "P2") (pinfunction "GND_P2") (pintype "bidirectional"))
      (node (ref "LDO_6") (pin "P3") (pinfunction "GND_P3") (pintype "bidirectional"))
      (node (ref "LDO_6") (pin "P4") (pinfunction "GND_P4") (pintype "bidirectional"))
      (node (ref "LDO_6") (pin "P5") (pinfunction "GND_P5") (pintype "bidirectional"))
      (node (ref "LDO_6") (pin "PAD") (pinfunction "GND_PAD") (pintype "bidirectional"))
      (node (ref "LDO_7") (pin "4") (pinfunction "GND_4") (pintype "bidirectional"))
      (node (ref "LDO_7") (pin "P1") (pinfunction "GND_P1") (pintype "bidirectional"))
      (node (ref "LDO_7") (pin "P2") (pinfunction "GND_P2") (pintype "bidirectional"))
      (node (ref "LDO_7") (pin "P3") (pinfunction "GND_P3") (pintype "bidirectional"))
      (node (ref "LDO_7") (pin "P4") (pinfunction "GND_P4") (pintype "bidirectional"))
      (node (ref "LDO_7") (pin "P5") (pinfunction "GND_P5") (pintype "bidirectional"))
      (node (ref "LDO_7") (pin "PAD") (pinfunction "GND_PAD") (pintype "bidirectional"))
      (node (ref "LDO_8") (pin "4") (pinfunction "GND_4") (pintype "bidirectional"))
      (node (ref "LDO_8") (pin "P1") (pinfunction "GND_P1") (pintype "bidirectional"))
      (node (ref "LDO_8") (pin "P2") (pinfunction "GND_P2") (pintype "bidirectional"))
      (node (ref "LDO_8") (pin "P3") (pinfunction "GND_P3") (pintype "bidirectional"))
      (node (ref "LDO_8") (pin "P4") (pinfunction "GND_P4") (pintype "bidirectional"))
      (node (ref "LDO_8") (pin "P5") (pinfunction "GND_P5") (pintype "bidirectional"))
      (node (ref "LDO_8") (pin "PAD") (pinfunction "GND_PAD") (pintype "bidirectional"))
      (node (ref "LDO_9") (pin "4") (pinfunction "GND_4") (pintype "bidirectional"))
      (node (ref "LDO_9") (pin "P1") (pinfunction "GND_P1") (pintype "bidirectional"))
      (node (ref "LDO_9") (pin "P2") (pinfunction "GND_P2") (pintype "bidirectional"))
      (node (ref "LDO_9") (pin "P3") (pinfunction "GND_P3") (pintype "bidirectional"))
      (node (ref "LDO_9") (pin "P4") (pinfunction "GND_P4") (pintype "bidirectional"))
      (node (ref "LDO_9") (pin "P5") (pinfunction "GND_P5") (pintype "bidirectional"))
      (node (ref "LDO_9") (pin "PAD") (pinfunction "GND_PAD") (pintype "bidirectional"))
      (node (ref "LED1") (pin "C") (pinfunction "C_C") (pintype "passive"))
      (node (ref "LNA_1") (pin "2") (pinfunction "GND_2") (pintype "bidirectional"))
      (node (ref "LNA_1") (pin "4") (pinfunction "GND_1_4") (pintype "bidirectional"))
      (node (ref "LNA_10") (pin "2") (pinfunction "GND_2") (pintype "bidirectional"))
      (node (ref "LNA_10") (pin "4") (pinfunction "GND_1_4") (pintype "bidirectional"))
      (node (ref "LNA_11") (pin "2") (pinfunction "GND_2") (pintype "bidirectional"))
      (node (ref "LNA_11") (pin "4") (pinfunction "GND_1_4") (pintype "bidirectional"))
      (node (ref "LNA_2") (pin "2") (pinfunction "GND_2") (pintype "bidirectional"))
      (node (ref "LNA_2") (pin "4") (pinfunction "GND_1_4") (pintype "bidirectional"))
      (node (ref "LNA_3") (pin "2") (pinfunction "GND_2") (pintype "bidirectional"))
      (node (ref "LNA_3") (pin "4") (pinfunction "GND_1_4") (pintype "bidirectional"))
      (node (ref "LNA_4") (pin "2") (pinfunction "GND_2") (pintype "bidirectional"))
      (node (ref "LNA_4") (pin "4") (pinfunction "GND_1_4") (pintype "bidirectional"))
      (node (ref "LNA_5") (pin "2") (pinfunction "GND_2") (pintype "bidirectional"))
      (node (ref "LNA_5") (pin "4") (pinfunction "GND_1_4") (pintype "bidirectional"))
      (node (ref "LNA_6") (pin "2") (pinfunction "GND_2") (pintype "bidirectional"))
      (node (ref "LNA_6") (pin "4") (pinfunction "GND_1_4") (pintype "bidirectional"))
      (node (ref "LNA_7") (pin "2") (pinfunction "GND_2") (pintype "bidirectional"))
      (node (ref "LNA_7") (pin "4") (pinfunction "GND_1_4") (pintype "bidirectional"))
      (node (ref "LNA_8") (pin "2") (pinfunction "GND_2") (pintype "bidirectional"))
      (node (ref "LNA_8") (pin "4") (pinfunction "GND_1_4") (pintype "bidirectional"))
      (node (ref "LNA_9") (pin "2") (pinfunction "GND_2") (pintype "bidirectional"))
      (node (ref "LNA_9") (pin "4") (pinfunction "GND_1_4") (pintype "bidirectional"))
      (node (ref "R1") (pin "2") (pinfunction "2_2") (pintype "passive"))
      (node (ref "R10") (pin "2") (pinfunction "2_2") (pintype "passive"))
      (node (ref "R13") (pin "1") (pinfunction "1_1") (pintype "passive"))
      (node (ref "R14") (pin "2") (pinfunction "2_2") (pintype "passive"))
      (node (ref "R17") (pin "1") (pinfunction "1_1") (pintype "passive"))
      (node (ref "R19") (pin "2") (pinfunction "2_2") (pintype "passive"))
      (node (ref "R205") (pin "1") (pinfunction "1_1") (pintype "passive"))
      (node (ref "R206") (pin "1") (pinfunction "1_1") (pintype "passive"))
      (node (ref "R23") (pin "2") (pinfunction "2_2") (pintype "passive"))
      (node (ref "R26") (pin "2") (pinfunction "2_2") (pintype "passive"))
      (node (ref "R29") (pin "2") (pinfunction "2_2") (pintype "passive"))
      (node (ref "R3") (pin "2") (pinfunction "2_2") (pintype "passive"))
      (node (ref "R32") (pin "2") (pinfunction "2_2") (pintype "passive"))
      (node (ref "R35") (pin "2") (pinfunction "2_2") (pintype "passive"))
      (node (ref "R38") (pin "2") (pinfunction "2_2") (pintype "passive"))
      (node (ref "R7") (pin "2") (pinfunction "2_2") (pintype "passive"))
      (node (ref "R8") (pin "1") (pinfunction "1_1") (pintype "passive"))
      (node (ref "SAW_1") (pin "2") (pinfunction "GND_1_2") (pintype "bidirectional"))
      (node (ref "SAW_1") (pin "3") (pinfunction "GND_2_3") (pintype "bidirectional"))
      (node (ref "SAW_1") (pin "4") (pinfunction "GND_3_4") (pintype "bidirectional"))
      (node (ref "SAW_1") (pin "5") (pinfunction "GND_4_5") (pintype "bidirectional"))
      (node (ref "SAW_1") (pin "6") (pinfunction "GND_5_6") (pintype "bidirectional"))
      (node (ref "SAW_1") (pin "7") (pinfunction "GND_6_7") (pintype "bidirectional"))
      (node (ref "SAW_10") (pin "1") (pinfunction "GND_1") (pintype "bidirectional"))
      (node (ref "SAW_10") (pin "3") (pinfunction "GND_1_3") (pintype "bidirectional"))
      (node (ref "SAW_10") (pin "4") (pinfunction "GND_2_4") (pintype "bidirectional"))
      (node (ref "SAW_10") (pin "6") (pinfunction "GND_3_6") (pintype "bidirectional"))
      (node (ref "SAW_11") (pin "1") (pinfunction "GND_1") (pintype "bidirectional"))
      (node (ref "SAW_11") (pin "3") (pinfunction "GND_1_3") (pintype "bidirectional"))
      (node (ref "SAW_11") (pin "4") (pinfunction "GND_2_4") (pintype "bidirectional"))
      (node (ref "SAW_11") (pin "6") (pinfunction "GND_3_6") (pintype "bidirectional"))
      (node (ref "SAW_12") (pin "1") (pinfunction "GND_1") (pintype "bidirectional"))
      (node (ref "SAW_12") (pin "3") (pinfunction "GND_1_3") (pintype "bidirectional"))
      (node (ref "SAW_12") (pin "4") (pinfunction "GND_2_4") (pintype "bidirectional"))
      (node (ref "SAW_12") (pin "6") (pinfunction "GND_3_6") (pintype "bidirectional"))
      (node (ref "SAW_2") (pin "1") (pinfunction "GND_1") (pintype "bidirectional"))
      (node (ref "SAW_2") (pin "3") (pinfunction "GND_1_3") (pintype "bidirectional"))
      (node (ref "SAW_2") (pin "4") (pinfunction "CASE_GND_4") (pintype "bidirectional"))
      (node (ref "SAW_2") (pin "5") (pinfunction "GND_2_5") (pintype "bidirectional"))
      (node (ref "SAW_2") (pin "7") (pinfunction "GND_3_7") (pintype "bidirectional"))
      (node (ref "SAW_2") (pin "8") (pinfunction "CASE_GND_1_8") (pintype "bidirectional"))
      (node (ref "SAW_3") (pin "1") (pinfunction "GND_1") (pintype "bidirectional"))
      (node (ref "SAW_3") (pin "3") (pinfunction "GND_1_3") (pintype "bidirectional"))
      (node (ref "SAW_3") (pin "4") (pinfunction "CASE_GND_4") (pintype "bidirectional"))
      (node (ref "SAW_3") (pin "5") (pinfunction "GND_2_5") (pintype "bidirectional"))
      (node (ref "SAW_3") (pin "7") (pinfunction "GND_3_7") (pintype "bidirectional"))
      (node (ref "SAW_3") (pin "8") (pinfunction "CASE_GND_1_8") (pintype "bidirectional"))
      (node (ref "SAW_4") (pin "1") (pinfunction "GND_1") (pintype "bidirectional"))
      (node (ref "SAW_4") (pin "3") (pinfunction "GND_1_3") (pintype "bidirectional"))
      (node (ref "SAW_4") (pin "4") (pinfunction "CASE_GND_4") (pintype "bidirectional"))
      (node (ref "SAW_4") (pin "5") (pinfunction "GND_2_5") (pintype "bidirectional"))
      (node (ref "SAW_4") (pin "7") (pinfunction "GND_3_7") (pintype "bidirectional"))
      (node (ref "SAW_4") (pin "8") (pinfunction "CASE_GND_1_8") (pintype "bidirectional"))
      (node (ref "SAW_5") (pin "1") (pinfunction "GND_1") (pintype "bidirectional"))
      (node (ref "SAW_5") (pin "3") (pinfunction "GND_1_3") (pintype "bidirectional"))
      (node (ref "SAW_5") (pin "4") (pinfunction "CASE_GND_4") (pintype "bidirectional"))
      (node (ref "SAW_5") (pin "5") (pinfunction "GND_2_5") (pintype "bidirectional"))
      (node (ref "SAW_5") (pin "7") (pinfunction "GND_3_7") (pintype "bidirectional"))
      (node (ref "SAW_5") (pin "8") (pinfunction "CASE_GND_1_8") (pintype "bidirectional"))
      (node (ref "SAW_6") (pin "1") (pinfunction "GND_1") (pintype "bidirectional"))
      (node (ref "SAW_6") (pin "3") (pinfunction "GND_1_3") (pintype "bidirectional"))
      (node (ref "SAW_6") (pin "4") (pinfunction "CASE_GND_4") (pintype "bidirectional"))
      (node (ref "SAW_6") (pin "5") (pinfunction "GND_2_5") (pintype "bidirectional"))
      (node (ref "SAW_6") (pin "7") (pinfunction "GND_3_7") (pintype "bidirectional"))
      (node (ref "SAW_6") (pin "8") (pinfunction "CASE_GND_1_8") (pintype "bidirectional"))
      (node (ref "SAW_7") (pin "1") (pinfunction "GND_1") (pintype "bidirectional"))
      (node (ref "SAW_7") (pin "3") (pinfunction "GND_1_3") (pintype "bidirectional"))
      (node (ref "SAW_7") (pin "4") (pinfunction "CASE_GND_4") (pintype "bidirectional"))
      (node (ref "SAW_7") (pin "5") (pinfunction "GND_2_5") (pintype "bidirectional"))
      (node (ref "SAW_7") (pin "7") (pinfunction "GND_3_7") (pintype "bidirectional"))
      (node (ref "SAW_7") (pin "8") (pinfunction "CASE_GND_1_8") (pintype "bidirectional"))
      (node (ref "SAW_8") (pin "1") (pinfunction "GND_1") (pintype "bidirectional"))
      (node (ref "SAW_8") (pin "3") (pinfunction "GND_1_3") (pintype "bidirectional"))
      (node (ref "SAW_8") (pin "4") (pinfunction "CASE_GND_4") (pintype "bidirectional"))
      (node (ref "SAW_8") (pin "5") (pinfunction "GND_2_5") (pintype "bidirectional"))
      (node (ref "SAW_8") (pin "7") (pinfunction "GND_3_7") (pintype "bidirectional"))
      (node (ref "SAW_8") (pin "8") (pinfunction "CASE_GND_1_8") (pintype "bidirectional"))
      (node (ref "SAW_9") (pin "1") (pinfunction "GND_1") (pintype "bidirectional"))
      (node (ref "SAW_9") (pin "3") (pinfunction "GND_1_3") (pintype "bidirectional"))
      (node (ref "SAW_9") (pin "4") (pinfunction "GND_2_4") (pintype "bidirectional"))
      (node (ref "SAW_9") (pin "6") (pinfunction "GND_3_6") (pintype "bidirectional"))
      (node (ref "X1") (pin "2") (pinfunction "GND_2") (pintype "power_in"))
      (node (ref "X10") (pin "2") (pinfunction "GND_2") (pintype "power_in"))
      (node (ref "X11") (pin "2") (pinfunction "GND_2") (pintype "power_in"))
      (node (ref "X12") (pin "2") (pinfunction "GND_2") (pintype "power_in"))
      (node (ref "X13") (pin "2") (pinfunction "GND_2") (pintype "power_in"))
      (node (ref "X14") (pin "2") (pinfunction "GND_2") (pintype "power_in"))
      (node (ref "X15") (pin "2") (pinfunction "GND_2") (pintype "power_in"))
      (node (ref "X16") (pin "2") (pinfunction "GND_2") (pintype "power_in"))
      (node (ref "X17") (pin "2") (pinfunction "GND_2") (pintype "power_in"))
      (node (ref "X18") (pin "2") (pinfunction "GND_2") (pintype "power_in"))
      (node (ref "X19") (pin "2") (pinfunction "GND_2") (pintype "power_in"))
      (node (ref "X2") (pin "2") (pinfunction "GND_2") (pintype "power_in"))
      (node (ref "X20") (pin "2") (pinfunction "GND_2") (pintype "power_in"))
      (node (ref "X21") (pin "2") (pinfunction "GND_2") (pintype "power_in"))
      (node (ref "X22") (pin "2") (pinfunction "GND_2") (pintype "power_in"))
      (node (ref "X23") (pin "2") (pinfunction "GND_2") (pintype "power_in"))
      (node (ref "X24") (pin "2") (pinfunction "GND_2") (pintype "power_in"))
      (node (ref "X25") (pin "2") (pinfunction "GND_2") (pintype "power_in"))
      (node (ref "X26") (pin "2") (pinfunction "GND_2") (pintype "power_in"))
      (node (ref "X27") (pin "2") (pinfunction "GND_2") (pintype "power_in"))
      (node (ref "X28") (pin "2") (pinfunction "GND_2") (pintype "power_in"))
      (node (ref "X29") (pin "2") (pinfunction "GND_2") (pintype "power_in"))
      (node (ref "X3") (pin "2") (pinfunction "GND_2") (pintype "power_in"))
      (node (ref "X30") (pin "2") (pinfunction "GND_2") (pintype "power_in"))
      (node (ref "X33") (pin "2") (pinfunction "GND_2") (pintype "power_in"))
      (node (ref "X4") (pin "2") (pinfunction "GND_2") (pintype "power_in"))
      (node (ref "X5") (pin "2") (pinfunction "GND_2") (pintype "power_in"))
      (node (ref "X6") (pin "2") (pinfunction "GND_2") (pintype "power_in"))
      (node (ref "X7") (pin "2") (pinfunction "GND_2") (pintype "power_in"))
      (node (ref "X8") (pin "2") (pinfunction "GND_2") (pintype "power_in"))
      (node (ref "X9") (pin "2") (pinfunction "GND_2") (pintype "power_in"))
    )
    (net (code "7") (name "Net-(C2-Pad1)") (class "Default")
      (node (ref "C2") (pin "1") (pinfunction "1_1") (pintype "passive"))
      (node (ref "C3") (pin "1") (pinfunction "1_1") (pintype "passive"))
      (node (ref "C54") (pin "2") (pinfunction "2_2") (pintype "passive"))
      (node (ref "C56") (pin "OUT") (pinfunction "OUT_OUT") (pintype "bidirectional"))
      (node (ref "L1") (pin "2") (pinfunction "2_2") (pintype "passive"))
      (node (ref "R2") (pin "1") (pinfunction "1_1") (pintype "passive"))
      (node (ref "TP_1") (pin "TP") (pinfunction "TP_TP") (pintype "input"))
    )
    (net (code "8") (name "Net-(C10-Pad1)") (class "Default")
      (node (ref "C10") (pin "1") (pinfunction "1_1") (pintype "passive"))
      (node (ref "C11") (pin "1") (pinfunction "1_1") (pintype "passive"))
      (node (ref "C63") (pin "2") (pinfunction "2_2") (pintype "passive"))
      (node (ref "C65") (pin "OUT") (pinfunction "OUT_OUT") (pintype "bidirectional"))
      (node (ref "L7") (pin "1") (pinfunction "1_1") (pintype "passive"))
      (node (ref "R9") (pin "1") (pinfunction "1_1") (pintype "passive"))
      (node (ref "TP_3") (pin "TP") (pinfunction "TP_TP") (pintype "input"))
    )
    (net (code "9") (name "Net-(C14-Pad1)") (class "Default")
      (node (ref "C14") (pin "1") (pinfunction "1_1") (pintype "passive"))
      (node (ref "X9") (pin "1") (pinfunction "1_1") (pintype "passive"))
    )
    (net (code "10") (name "Net-(C15-Pad1)") (class "Default")
      (node (ref "C15") (pin "1") (pinfunction "1_1") (pintype "passive"))
      (node (ref "C16") (pin "1") (pinfunction "1_1") (pintype "passive"))
      (node (ref "C67") (pin "2") (pinfunction "2_2") (pintype "passive"))
      (node (ref "C69") (pin "OUT") (pinfunction "OUT_OUT") (pintype "bidirectional"))
      (node (ref "L10") (pin "2") (pinfunction "2_2") (pintype "passive"))
      (node (ref "R12") (pin "1") (pinfunction "1_1") (pintype "passive"))
      (node (ref "TP_4") (pin "TP") (pinfunction "TP_TP") (pintype "input"))
    )
    (net (code "11") (name "Net-(C19-Pad1)") (class "Default")
      (node (ref "C19") (pin "1") (pinfunction "1_1") (pintype "passive"))
      (node (ref "C20") (pin "1") (pinfunction "1_1") (pintype "passive"))
      (node (ref "C71") (pin "2") (pinfunction "2_2") (pintype "passive"))
      (node (ref "C75") (pin "OUT") (pinfunction "OUT_OUT") (pintype "bidirectional"))
      (node (ref "L11") (pin "2") (pinfunction "2_2") (pintype "passive"))
      (node (ref "R16") (pin "1") (pinfunction "1_1") (pintype "passive"))
      (node (ref "TP_5") (pin "TP") (pinfunction "TP_TP") (pintype "input"))
    )
    (net (code "12") (name "Net-(C23-Pad1)") (class "Default")
      (node (ref "C23") (pin "1") (pinfunction "1_1") (pintype "passive"))
      (node (ref "C24") (pin "1") (pinfunction "1_1") (pintype "passive"))
      (node (ref "C77") (pin "2") (pinfunction "2_2") (pintype "passive"))
      (node (ref "C79") (pin "OUT") (pinfunction "OUT_OUT") (pintype "bidirectional"))
      (node (ref "L12") (pin "1") (pinfunction "1_1") (pintype "passive"))
      (node (ref "R22") (pin "1") (pinfunction "1_1") (pintype "passive"))
      (node (ref "TP_6") (pin "TP") (pinfunction "TP_TP") (pintype "input"))
    )
    (net (code "13") (name "Net-(C26-Pad1)") (class "Default")
      (node (ref "C26") (pin "1") (pinfunction "1_1") (pintype "passive"))
      (node (ref "X17") (pin "1") (pinfunction "1_1") (pintype "passive"))
    )
    (net (code "14") (name "Net-(C27-Pad1)") (class "Default")
      (node (ref "C27") (pin "1") (pinfunction "1_1") (pintype "passive"))
      (node (ref "C28") (pin "1") (pinfunction "1_1") (pintype "passive"))
      (node (ref "C81") (pin "2") (pinfunction "2_2") (pintype "passive"))
      (node (ref "C83") (pin "OUT") (pinfunction "OUT_OUT") (pintype "bidirectional"))
      (node (ref "L13") (pin "2") (pinfunction "2_2") (pintype "passive"))
      (node (ref "R25") (pin "1") (pinfunction "1_1") (pintype "passive"))
      (node (ref "TP_7") (pin "TP") (pinfunction "TP_TP") (pintype "input"))
    )
    (net (code "15") (name "Net-(C31-Pad1)") (class "Default")
      (node (ref "C31") (pin "1") (pinfunction "1_1") (pintype "passive"))
      (node (ref "C32") (pin "1") (pinfunction "1_1") (pintype "passive"))
      (node (ref "C85") (pin "2") (pinfunction "2_2") (pintype "passive"))
      (node (ref "C87") (pin "OUT") (pinfunction "OUT_OUT") (pintype "bidirectional"))
      (node (ref "L14") (pin "2") (pinfunction "2_2") (pintype "passive"))
      (node (ref "R28") (pin "1") (pinfunction "1_1") (pintype "passive"))
      (node (ref "TP_8") (pin "TP") (pinfunction "TP_TP") (pintype "input"))
    )
    (net (code "16") (name "Net-(C35-Pad1)") (class "Default")
      (node (ref "C35") (pin "1") (pinfunction "1_1") (pintype "passive"))
      (node (ref "C36") (pin "1") (pinfunction "1_1") (pintype "passive"))
      (node (ref "C89") (pin "2") (pinfunction "2_2") (pintype "passive"))
      (node (ref "C91") (pin "OUT") (pinfunction "OUT_OUT") (pintype "bidirectional"))
      (node (ref "L15") (pin "2") (pinfunction "2_2") (pintype "passive"))
      (node (ref "R31") (pin "1") (pinfunction "1_1") (pintype "passive"))
      (node (ref "TP_9") (pin "TP") (pinfunction "TP_TP") (pintype "input"))
    )
    (net (code "17") (name "Net-(C38-Pad1)") (class "Default")
      (node (ref "C38") (pin "1") (pinfunction "1_1") (pintype "passive"))
      (node (ref "R5") (pin "1") (pinfunction "1_1") (pintype "passive"))
    )
    (net (code "18") (name "Net-(C38-Pad2)") (class "Default")
      (node (ref "C38") (pin "2") (pinfunction "2_2") (pintype "passive"))
      (node (ref "L16") (pin "1") (pinfunction "1_1") (pintype "passive"))
    )
    (net (code "19") (name "Net-(C39-Pad1)") (class "Default")
      (node (ref "C39") (pin "1") (pinfunction "1_1") (pintype "passive"))
      (node (ref "C43") (pin "1") (pinfunction "1_1") (pintype "passive"))
      (node (ref "C51") (pin "1") (pinfunction "1_1") (pintype "passive"))
      (node (ref "L16") (pin "2") (pinfunction "2_2") (pintype "passive"))
      (node (ref "L17") (pin "2") (pinfunction "2_2") (pintype "passive"))
    )
    (net (code "20") (name "Net-(C40-Pad1)") (class "Default")
      (node (ref "C40") (pin "1") (pinfunction "1_1") (pintype "passive"))
      (node (ref "C41") (pin "1") (pinfunction "1_1") (pintype "passive"))
      (node (ref "C93") (pin "2") (pinfunction "2_2") (pintype "passive"))
      (node (ref "C95") (pin "OUT") (pinfunction "OUT_OUT") (pintype "bidirectional"))
      (node (ref "L18") (pin "2") (pinfunction "2_2") (pintype "passive"))
      (node (ref "R34") (pin "1") (pinfunction "1_1") (pintype "passive"))
      (node (ref "TP_10") (pin "TP") (pinfunction "TP_TP") (pintype "input"))
    )
    (net (code "21") (name "Net-(C42-Pad2)") (class "Default")
      (node (ref "C42") (pin "2") (pinfunction "2_2") (pintype "passive"))
      (node (ref "R11") (pin "2") (pinfunction "2_2") (pintype "passive"))
      (node (ref "X27") (pin "1") (pinfunction "1_1") (pintype "passive"))
    )
    (net (code "22") (name "Net-(C43-Pad2)") (class "Default")
      (node (ref "C43") (pin "2") (pinfunction "2_2") (pintype "passive"))
      (node (ref "L20") (pin "1") (pinfunction "1_1") (pintype "passive"))
    )
    (net (code "23") (name "Net-(C44-Pad1)") (class "Default")
      (node (ref "C44") (pin "1") (pinfunction "1_1") (pintype "passive"))
      (node (ref "C45") (pin "1") (pinfunction "1_1") (pintype "passive"))
      (node (ref "C97") (pin "2") (pinfunction "2_2") (pintype "passive"))
      (node (ref "C99") (pin "OUT") (pinfunction "OUT_OUT") (pintype "bidirectional"))
      (node (ref "L21") (pin "2") (pinfunction "2_2") (pintype "passive"))
      (node (ref "R37") (pin "1") (pinfunction "1_1") (pintype "passive"))
      (node (ref "TP_11") (pin "TP") (pinfunction "TP_TP") (pintype "input"))
    )
    (net (code "24") (name "Net-(C46-Pad1)") (class "Default")
      (node (ref "C46") (pin "1") (pinfunction "1_1") (pintype "passive"))
      (node (ref "C50") (pin "1") (pinfunction "1_1") (pintype "passive"))
      (node (ref "C52") (pin "1") (pinfunction "1_1") (pintype "passive"))
      (node (ref "L20") (pin "2") (pinfunction "2_2") (pintype "passive"))
      (node (ref "L22") (pin "2") (pinfunction "2_2") (pintype "passive"))
    )
    (net (code "25") (name "Net-(C47-Pad1)") (class "Default")
      (node (ref "C47") (pin "1") (pinfunction "1_1") (pintype "passive"))
      (node (ref "R15") (pin "1") (pinfunction "1_1") (pintype "passive"))
    )
    (net (code "26") (name "Net-(C47-Pad2)") (class "Default")
      (node (ref "C47") (pin "2") (pinfunction "2_2") (pintype "passive"))
      (node (ref "L23") (pin "1") (pinfunction "1_1") (pintype "passive"))
    )
    (net (code "27") (name "Net-(C49-Pad2)") (class "Default")
      (node (ref "C49") (pin "2") (pinfunction "2_2") (pintype "passive"))
      (node (ref "L30") (pin "1") (pinfunction "1_1") (pintype "passive"))
    )
    (net (code "28") (name "Net-(C50-Pad2)") (class "Default")
      (node (ref "C50") (pin "2") (pinfunction "2_2") (pintype "passive"))
      (node (ref "L25") (pin "1") (pinfunction "1_1") (pintype "passive"))
    )
    (net (code "29") (name "Net-(C55-PadOUT)") (class "Default")
      (node (ref "C55") (pin "OUT") (pinfunction "OUT_OUT") (pintype "bidirectional"))
      (node (ref "LDO_1") (pin "7") (pinfunction "IN_7") (pintype "bidirectional"))
      (node (ref "LDO_1") (pin "8") (pinfunction "IN_8") (pintype "bidirectional"))
    )
    (net (code "30") (name "Net-(C56-PadIN)") (class "Default")
      (node (ref "C56") (pin "IN") (pinfunction "IN_IN") (pintype "bidirectional"))
      (node (ref "LDO_1") (pin "1") (pinfunction "OUT_1") (pintype "bidirectional"))
      (node (ref "LDO_1") (pin "2") (pinfunction "OUT_2") (pintype "bidirectional"))
    )
    (net (code "31") (name "Net-(C57-Pad1)") (class "Default")
      (node (ref "C57") (pin "1") (pinfunction "1_1") (pintype "passive"))
      (node (ref "L25") (pin "2") (pinfunction "2_2") (pintype "passive"))
      (node (ref "R8") (pin "2") (pinfunction "2_2") (pintype "passive"))
      (node (ref "X26") (pin "1") (pinfunction "1_1") (pintype "passive"))
    )
    (net (code "32") (name "Net-(C59-Pad2)") (class "Default")
      (node (ref "C59") (pin "2") (pinfunction "2_2") (pintype "passive"))
      (node (ref "C6") (pin "1") (pinfunction "1_1") (pintype "passive"))
      (node (ref "C61") (pin "OUT") (pinfunction "OUT_OUT") (pintype "bidirectional"))
      (node (ref "C7") (pin "1") (pinfunction "1_1") (pintype "passive"))
      (node (ref "L4") (pin "2") (pinfunction "2_2") (pintype "passive"))
      (node (ref "R6") (pin "1") (pinfunction "1_1") (pintype "passive"))
      (node (ref "TP_2") (pin "TP") (pinfunction "TP_TP") (pintype "input"))
    )
    (net (code "33") (name "Net-(C60-PadOUT)") (class "Default")
      (node (ref "C60") (pin "OUT") (pinfunction "OUT_OUT") (pintype "bidirectional"))
      (node (ref "LDO_2") (pin "7") (pinfunction "IN_7") (pintype "bidirectional"))
      (node (ref "LDO_2") (pin "8") (pinfunction "IN_8") (pintype "bidirectional"))
    )
    (net (code "34") (name "Net-(C61-PadIN)") (class "Default")
      (node (ref "C61") (pin "IN") (pinfunction "IN_IN") (pintype "bidirectional"))
      (node (ref "LDO_2") (pin "1") (pinfunction "OUT_1") (pintype "bidirectional"))
      (node (ref "LDO_2") (pin "2") (pinfunction "OUT_2") (pintype "bidirectional"))
    )
    (net (code "35") (name "Net-(C64-PadOUT)") (class "Default")
      (node (ref "C64") (pin "OUT") (pinfunction "OUT_OUT") (pintype "bidirectional"))
      (node (ref "LDO_3") (pin "7") (pinfunction "IN_7") (pintype "bidirectional"))
      (node (ref "LDO_3") (pin "8") (pinfunction "IN_8") (pintype "bidirectional"))
    )
    (net (code "36") (name "Net-(C65-PadIN)") (class "Default")
      (node (ref "C65") (pin "IN") (pinfunction "IN_IN") (pintype "bidirectional"))
      (node (ref "LDO_3") (pin "1") (pinfunction "OUT_1") (pintype "bidirectional"))
      (node (ref "LDO_3") (pin "2") (pinfunction "OUT_2") (pintype "bidirectional"))
    )
    (net (code "37") (name "Net-(C68-PadOUT)") (class "Default")
      (node (ref "C68") (pin "OUT") (pinfunction "OUT_OUT") (pintype "bidirectional"))
      (node (ref "LDO_4") (pin "7") (pinfunction "IN_7") (pintype "bidirectional"))
      (node (ref "LDO_4") (pin "8") (pinfunction "IN_8") (pintype "bidirectional"))
    )
    (net (code "38") (name "Net-(C69-PadIN)") (class "Default")
      (node (ref "C69") (pin "IN") (pinfunction "IN_IN") (pintype "bidirectional"))
      (node (ref "LDO_4") (pin "1") (pinfunction "OUT_1") (pintype "bidirectional"))
      (node (ref "LDO_4") (pin "2") (pinfunction "OUT_2") (pintype "bidirectional"))
    )
    (net (code "39") (name "Net-(C72-Pad1)") (class "Default")
      (node (ref "C72") (pin "1") (pinfunction "1_1") (pintype "passive"))
      (node (ref "R11") (pin "1") (pinfunction "1_1") (pintype "passive"))
    )
    (net (code "40") (name "Net-(C72-Pad2)") (class "Default")
      (node (ref "C72") (pin "2") (pinfunction "2_2") (pintype "passive"))
      (node (ref "L19") (pin "1") (pinfunction "1_1") (pintype "passive"))
    )
    (net (code "41") (name "Net-(C74-PadOUT)") (class "Default")
      (node (ref "C74") (pin "OUT") (pinfunction "OUT_OUT") (pintype "bidirectional"))
      (node (ref "LDO_5") (pin "7") (pinfunction "IN_7") (pintype "bidirectional"))
      (node (ref "LDO_5") (pin "8") (pinfunction "IN_8") (pintype "bidirectional"))
    )
    (net (code "42") (name "Net-(C75-PadIN)") (class "Default")
      (node (ref "C75") (pin "IN") (pinfunction "IN_IN") (pintype "bidirectional"))
      (node (ref "LDO_5") (pin "1") (pinfunction "OUT_1") (pintype "bidirectional"))
      (node (ref "LDO_5") (pin "2") (pinfunction "OUT_2") (pintype "bidirectional"))
    )
    (net (code "43") (name "Net-(C78-PadOUT)") (class "Default")
      (node (ref "C78") (pin "OUT") (pinfunction "OUT_OUT") (pintype "bidirectional"))
      (node (ref "LDO_6") (pin "7") (pinfunction "IN_7") (pintype "bidirectional"))
      (node (ref "LDO_6") (pin "8") (pinfunction "IN_8") (pintype "bidirectional"))
    )
    (net (code "44") (name "Net-(C79-PadIN)") (class "Default")
      (node (ref "C79") (pin "IN") (pinfunction "IN_IN") (pintype "bidirectional"))
      (node (ref "LDO_6") (pin "1") (pinfunction "OUT_1") (pintype "bidirectional"))
      (node (ref "LDO_6") (pin "2") (pinfunction "OUT_2") (pintype "bidirectional"))
    )
    (net (code "45") (name "Net-(C82-PadOUT)") (class "Default")
      (node (ref "C82") (pin "OUT") (pinfunction "OUT_OUT") (pintype "bidirectional"))
      (node (ref "LDO_7") (pin "7") (pinfunction "IN_7") (pintype "bidirectional"))
      (node (ref "LDO_7") (pin "8") (pinfunction "IN_8") (pintype "bidirectional"))
    )
    (net (code "46") (name "Net-(C83-PadIN)") (class "Default")
      (node (ref "C83") (pin "IN") (pinfunction "IN_IN") (pintype "bidirectional"))
      (node (ref "LDO_7") (pin "1") (pinfunction "OUT_1") (pintype "bidirectional"))
      (node (ref "LDO_7") (pin "2") (pinfunction "OUT_2") (pintype "bidirectional"))
    )
    (net (code "47") (name "Net-(C86-PadOUT)") (class "Default")
      (node (ref "C86") (pin "OUT") (pinfunction "OUT_OUT") (pintype "bidirectional"))
      (node (ref "LDO_8") (pin "7") (pinfunction "IN_7") (pintype "bidirectional"))
      (node (ref "LDO_8") (pin "8") (pinfunction "IN_8") (pintype "bidirectional"))
    )
    (net (code "48") (name "Net-(C87-PadIN)") (class "Default")
      (node (ref "C87") (pin "IN") (pinfunction "IN_IN") (pintype "bidirectional"))
      (node (ref "LDO_8") (pin "1") (pinfunction "OUT_1") (pintype "bidirectional"))
      (node (ref "LDO_8") (pin "2") (pinfunction "OUT_2") (pintype "bidirectional"))
    )
    (net (code "49") (name "Net-(C90-PadOUT)") (class "Default")
      (node (ref "C90") (pin "OUT") (pinfunction "OUT_OUT") (pintype "bidirectional"))
      (node (ref "LDO_9") (pin "7") (pinfunction "IN_7") (pintype "bidirectional"))
      (node (ref "LDO_9") (pin "8") (pinfunction "IN_8") (pintype "bidirectional"))
    )
    (net (code "50") (name "Net-(C91-PadIN)") (class "Default")
      (node (ref "C91") (pin "IN") (pinfunction "IN_IN") (pintype "bidirectional"))
      (node (ref "LDO_9") (pin "1") (pinfunction "OUT_1") (pintype "bidirectional"))
      (node (ref "LDO_9") (pin "2") (pinfunction "OUT_2") (pintype "bidirectional"))
    )
    (net (code "51") (name "Net-(C94-PadOUT)") (class "Default")
      (node (ref "C94") (pin "OUT") (pinfunction "OUT_OUT") (pintype "bidirectional"))
      (node (ref "LDO_10") (pin "7") (pinfunction "IN_7") (pintype "bidirectional"))
      (node (ref "LDO_10") (pin "8") (pinfunction "IN_8") (pintype "bidirectional"))
    )
    (net (code "52") (name "Net-(C95-PadIN)") (class "Default")
      (node (ref "C95") (pin "IN") (pinfunction "IN_IN") (pintype "bidirectional"))
      (node (ref "LDO_10") (pin "1") (pinfunction "OUT_1") (pintype "bidirectional"))
      (node (ref "LDO_10") (pin "2") (pinfunction "OUT_2") (pintype "bidirectional"))
    )
    (net (code "53") (name "Net-(C98-PadOUT)") (class "Default")
      (node (ref "C98") (pin "OUT") (pinfunction "OUT_OUT") (pintype "bidirectional"))
      (node (ref "LDO_11") (pin "7") (pinfunction "IN_7") (pintype "bidirectional"))
      (node (ref "LDO_11") (pin "8") (pinfunction "IN_8") (pintype "bidirectional"))
    )
    (net (code "54") (name "Net-(C99-PadIN)") (class "Default")
      (node (ref "C99") (pin "IN") (pinfunction "IN_IN") (pintype "bidirectional"))
      (node (ref "LDO_11") (pin "1") (pinfunction "OUT_1") (pintype "bidirectional"))
      (node (ref "LDO_11") (pin "2") (pinfunction "OUT_2") (pintype "bidirectional"))
    )
    (net (code "55") (name "Net-(C100-Pad1)") (class "Default")
      (node (ref "C100") (pin "1") (pinfunction "1_1") (pintype "passive"))
      (node (ref "C101") (pin "1") (pinfunction "1_1") (pintype "passive"))
      (node (ref "C103") (pin "1") (pinfunction "1_1") (pintype "passive"))
      (node (ref "L30") (pin "2") (pinfunction "2_2") (pintype "passive"))
      (node (ref "L32") (pin "2") (pinfunction "2_2") (pintype "passive"))
    )
    (net (code "56") (name "Net-(C101-Pad2)") (class "Default")
      (node (ref "C101") (pin "2") (pinfunction "2_2") (pintype "passive"))
      (node (ref "L33") (pin "1") (pinfunction "1_1") (pintype "passive"))
    )
    (net (code "57") (name "Net-(C102-Pad1)") (class "Default")
      (node (ref "C102") (pin "1") (pinfunction "1_1") (pintype "passive"))
      (node (ref "C48") (pin "1") (pinfunction "1_1") (pintype "passive"))
      (node (ref "C49") (pin "1") (pinfunction "1_1") (pintype "passive"))
      (node (ref "L23") (pin "2") (pinfunction "2_2") (pintype "passive"))
      (node (ref "L24") (pin "2") (pinfunction "2_2") (pintype "passive"))
    )
    (net (code "58") (name "Net-(C104-Pad1)") (class "Default")
      (node (ref "C104") (pin "1") (pinfunction "1_1") (pintype "passive"))
      (node (ref "C107") (pin "1") (pinfunction "1_1") (pintype "passive"))
      (node (ref "C73") (pin "1") (pinfunction "1_1") (pintype "passive"))
      (node (ref "L19") (pin "2") (pinfunction "2_2") (pintype "passive"))
      (node (ref "L26") (pin "2") (pinfunction "2_2") (pintype "passive"))
    )
    (net (code "59") (name "Net-(C104-Pad2)") (class "Default")
      (node (ref "C104") (pin "2") (pinfunction "2_2") (pintype "passive"))
      (node (ref "L27") (pin "1") (pinfunction "1_1") (pintype "passive"))
    )
    (net (code "60") (name "Net-(C105-Pad1)") (class "Default")
      (node (ref "C105") (pin "1") (pinfunction "1_1") (pintype "passive"))
      (node (ref "C106") (pin "1") (pinfunction "1_1") (pintype "passive"))
      (node (ref "C108") (pin "1") (pinfunction "1_1") (pintype "passive"))
      (node (ref "L27") (pin "2") (pinfunction "2_2") (pintype "passive"))
      (node (ref "L28") (pin "2") (pinfunction "2_2") (pintype "passive"))
    )
    (net (code "61") (name "Net-(C106-Pad2)") (class "Default")
      (node (ref "C106") (pin "2") (pinfunction "2_2") (pintype "passive"))
      (node (ref "L29") (pin "1") (pinfunction "1_1") (pintype "passive"))
    )
    (net (code "62") (name "Net-(C109-Pad1)") (class "Default")
      (node (ref "C109") (pin "1") (pinfunction "1_1") (pintype "passive"))
      (node (ref "L29") (pin "2") (pinfunction "2_2") (pintype "passive"))
      (node (ref "R13") (pin "2") (pinfunction "2_2") (pintype "passive"))
      (node (ref "X28") (pin "1") (pinfunction "1_1") (pintype "passive"))
    )
    (net (code "63") (name "Net-(C110-Pad2)") (class "Default")
      (node (ref "C110") (pin "2") (pinfunction "2_2") (pintype "passive"))
      (node (ref "R15") (pin "2") (pinfunction "2_2") (pintype "passive"))
      (node (ref "X29") (pin "1") (pinfunction "1_1") (pintype "passive"))
    )
    (net (code "64") (name "Net-(C459-PadIN)") (class "Default")
      (node (ref "C459") (pin "IN") (pinfunction "IN_IN") (pintype "bidirectional"))
      (node (ref "IC58") (pin "34") (pinfunction "VOUT_34") (pintype "bidirectional"))
      (node (ref "IC58") (pin "35") (pinfunction "VOUT_35") (pintype "bidirectional"))
      (node (ref "IC58") (pin "36") (pinfunction "VOUT_36") (pintype "bidirectional"))
      (node (ref "IC58") (pin "37") (pinfunction "VOUT_37") (pintype "bidirectional"))
      (node (ref "IC58") (pin "38") (pinfunction "VOUT_38") (pintype "bidirectional"))
      (node (ref "IC58") (pin "41") (pinfunction "VOUT_41") (pintype "bidirectional"))
    )
    (net (code "65") (name "Net-(C500-IN)") (class "Default")
      (node (ref "C500") (pin "1") (pinfunction "IN_1") (pintype "passive"))
      (node (ref "L31") (pin "2") (pinfunction "2_2") (pintype "passive"))
    )
    (net (code "66") (name "Net-(C500-OUT)") (class "Default")
      (node (ref "C481") (pin "1") (pinfunction "1_1") (pintype "passive"))
      (node (ref "C482") (pin "1") (pinfunction "1_1") (pintype "passive"))
      (node (ref "C483") (pin "+") (pinfunction "+_+") (pintype "passive"))
      (node (ref "C484") (pin "+") (pinfunction "+_+") (pintype "passive"))
      (node (ref "C489") (pin "1") (pinfunction "1_1") (pintype "passive"))
      (node (ref "C490") (pin "1") (pinfunction "1_1") (pintype "passive"))
      (node (ref "C491") (pin "1") (pinfunction "1_1") (pintype "passive"))
      (node (ref "C492") (pin "1") (pinfunction "1_1") (pintype "passive"))
      (node (ref "C493") (pin "1") (pinfunction "1_1") (pintype "passive"))
      (node (ref "C500") (pin "2") (pinfunction "OUT_2") (pintype "passive"))
      (node (ref "IC58") (pin "1") (pinfunction "PVIN_1") (pintype "bidirectional"))
      (node (ref "IC58") (pin "11") (pinfunction "PVIN_11") (pintype "bidirectional"))
      (node (ref "IC58") (pin "12") (pinfunction "PVIN_12") (pintype "bidirectional"))
      (node (ref "IC58") (pin "3") (pinfunction "VIN_3") (pintype "bidirectional"))
      (node (ref "IC58") (pin "39") (pinfunction "PVIN_39") (pintype "bidirectional"))
      (node (ref "IC58") (pin "40") (pinfunction "PVIN_40") (pintype "bidirectional"))
      (node (ref "R4") (pin "1") (pinfunction "1_1") (pintype "passive"))
    )
    (net (code "67") (name "Net-(IC1-SUM_PORT)") (class "Default")
      (node (ref "IC1") (pin "3") (pinfunction "SUM_PORT_3") (pintype "bidirectional"))
      (node (ref "X33") (pin "1") (pinfunction "1_1") (pintype "passive"))
    )
    (net (code "68") (name "Net-(IC58-INH{slash}UVLO)") (class "Default")
      (node (ref "IC58") (pin "30") (pinfunction "INH/UVLO_30") (pintype "bidirectional"))
      (node (ref "R1") (pin "1") (pinfunction "1_1") (pintype "passive"))
      (node (ref "R4") (pin "2") (pinfunction "2_2") (pintype "passive"))
    )
    (net (code "69") (name "Net-(IC58-PH-Pad10)") (class "Default")
      (node (ref "IC58") (pin "10") (pinfunction "PH_10") (pintype "bidirectional"))
      (node (ref "IC58") (pin "13") (pinfunction "PH_13") (pintype "bidirectional"))
      (node (ref "IC58") (pin "14") (pinfunction "PH_14") (pintype "bidirectional"))
      (node (ref "IC58") (pin "15") (pinfunction "PH_15") (pintype "bidirectional"))
      (node (ref "IC58") (pin "16") (pinfunction "PH_16") (pintype "bidirectional"))
      (node (ref "IC58") (pin "17") (pinfunction "PH_17") (pintype "bidirectional"))
      (node (ref "IC58") (pin "18") (pinfunction "PH_18") (pintype "bidirectional"))
      (node (ref "IC58") (pin "19") (pinfunction "PH_19") (pintype "bidirectional"))
      (node (ref "IC58") (pin "42") (pinfunction "PH_42") (pintype "bidirectional"))
      (node (ref "IC58") (pin "42A") (pinfunction "PH_42A") (pintype "bidirectional"))
      (node (ref "IC58") (pin "42B") (pinfunction "PH_42B") (pintype "bidirectional"))
      (node (ref "IC58") (pin "42C") (pinfunction "PH_42C") (pintype "bidirectional"))
      (node (ref "IC58") (pin "42D") (pinfunction "PH_42D") (pintype "bidirectional"))
      (node (ref "IC58") (pin "42E") (pinfunction "PH_42E") (pintype "bidirectional"))
      (node (ref "IC58") (pin "42F") (pinfunction "PH_42F") (pintype "bidirectional"))
      (node (ref "IC58") (pin "42G") (pinfunction "PH_42G") (pintype "bidirectional"))
      (node (ref "IC58") (pin "42H") (pinfunction "PH_42H") (pintype "bidirectional"))
      (node (ref "IC58") (pin "42J") (pinfunction "PH_42J") (pintype "bidirectional"))
      (node (ref "IC58") (pin "42K") (pinfunction "PH_42K") (pintype "bidirectional"))
      (node (ref "IC58") (pin "42L") (pinfunction "PH_42L") (pintype "bidirectional"))
      (node (ref "IC58") (pin "42M") (pinfunction "PH_42M") (pintype "bidirectional"))
      (node (ref "IC58") (pin "42N") (pinfunction "PH_42N") (pintype "bidirectional"))
      (node (ref "IC58") (pin "42P") (pinfunction "PH_42P") (pintype "bidirectional"))
    )
    (net (code "70") (name "Net-(IC58-PWRGD)") (class "Default")
      (node (ref "IC58") (pin "8") (pinfunction "PWRGD_8") (pintype "bidirectional"))
      (node (ref "TP10") (pin "TP") (pinfunction "TP_TP") (pintype "input"))
    )
    (net (code "71") (name "Net-(IC58-RT_CLK)") (class "Default")
      (node (ref "IC58") (pin "22") (pinfunction "RT_CLK_22") (pintype "bidirectional"))
      (node (ref "R206") (pin "2") (pinfunction "2_2") (pintype "passive"))
    )
    (net (code "72") (name "Net-(IC58-VADJ)") (class "Default")
      (node (ref "IC58") (pin "26") (pinfunction "VADJ_26") (pintype "bidirectional"))
      (node (ref "R205") (pin "2") (pinfunction "2_2") (pintype "passive"))
    )
    (net (code "73") (name "Net-(J1B-S)") (class "Default")
      (node (ref "J1") (pin "2") (pinfunction "S_2") (pintype "passive"))
      (node (ref "L31") (pin "1") (pinfunction "1_1") (pintype "passive"))
    )
    (net (code "74") (name "Net-(LDO_1-FB{slash}SNS)") (class "Default")
      (node (ref "C54") (pin "1") (pinfunction "1_1") (pintype "passive"))
      (node (ref "LDO_1") (pin "3") (pinfunction "FB/SNS_3") (pintype "bidirectional"))
      (node (ref "R2") (pin "2") (pinfunction "2_2") (pintype "passive"))
      (node (ref "R3") (pin "1") (pinfunction "1_1") (pintype "passive"))
    )
    (net (code "75") (name "Net-(LDO_1-NR)") (class "Default")
      (node (ref "C53") (pin "1") (pinfunction "1_1") (pintype "passive"))
      (node (ref "LDO_1") (pin "6") (pinfunction "NR_6") (pintype "bidirectional"))
    )
    (net (code "76") (name "Net-(LDO_2-FB{slash}SNS)") (class "Default")
      (node (ref "C59") (pin "1") (pinfunction "1_1") (pintype "passive"))
      (node (ref "LDO_2") (pin "3") (pinfunction "FB/SNS_3") (pintype "bidirectional"))
      (node (ref "R6") (pin "2") (pinfunction "2_2") (pintype "passive"))
      (node (ref "R7") (pin "1") (pinfunction "1_1") (pintype "passive"))
    )
    (net (code "77") (name "Net-(LDO_2-NR)") (class "Default")
      (node (ref "C58") (pin "1") (pinfunction "1_1") (pintype "passive"))
      (node (ref "LDO_2") (pin "6") (pinfunction "NR_6") (pintype "bidirectional"))
    )
    (net (code "78") (name "Net-(LDO_3-FB{slash}SNS)") (class "Default")
      (node (ref "C63") (pin "1") (pinfunction "1_1") (pintype "passive"))
      (node (ref "LDO_3") (pin "3") (pinfunction "FB/SNS_3") (pintype "bidirectional"))
      (node (ref "R10") (pin "1") (pinfunction "1_1") (pintype "passive"))
      (node (ref "R9") (pin "2") (pinfunction "2_2") (pintype "passive"))
    )
    (net (code "79") (name "Net-(LDO_3-NR)") (class "Default")
      (node (ref "C62") (pin "1") (pinfunction "1_1") (pintype "passive"))
      (node (ref "LDO_3") (pin "6") (pinfunction "NR_6") (pintype "bidirectional"))
    )
    (net (code "80") (name "Net-(LDO_4-FB{slash}SNS)") (class "Default")
      (node (ref "C67") (pin "1") (pinfunction "1_1") (pintype "passive"))
      (node (ref "LDO_4") (pin "3") (pinfunction "FB/SNS_3") (pintype "bidirectional"))
      (node (ref "R12") (pin "2") (pinfunction "2_2") (pintype "passive"))
      (node (ref "R14") (pin "1") (pinfunction "1_1") (pintype "passive"))
    )
    (net (code "81") (name "Net-(LDO_4-NR)") (class "Default")
      (node (ref "C66") (pin "1") (pinfunction "1_1") (pintype "passive"))
      (node (ref "LDO_4") (pin "6") (pinfunction "NR_6") (pintype "bidirectional"))
    )
    (net (code "82") (name "Net-(LDO_5-FB{slash}SNS)") (class "Default")
      (node (ref "C71") (pin "1") (pinfunction "1_1") (pintype "passive"))
      (node (ref "LDO_5") (pin "3") (pinfunction "FB/SNS_3") (pintype "bidirectional"))
      (node (ref "R16") (pin "2") (pinfunction "2_2") (pintype "passive"))
      (node (ref "R19") (pin "1") (pinfunction "1_1") (pintype "passive"))
    )
    (net (code "83") (name "Net-(LDO_5-NR)") (class "Default")
      (node (ref "C70") (pin "1") (pinfunction "1_1") (pintype "passive"))
      (node (ref "LDO_5") (pin "6") (pinfunction "NR_6") (pintype "bidirectional"))
    )
    (net (code "84") (name "Net-(LDO_6-FB{slash}SNS)") (class "Default")
      (node (ref "C77") (pin "1") (pinfunction "1_1") (pintype "passive"))
      (node (ref "LDO_6") (pin "3") (pinfunction "FB/SNS_3") (pintype "bidirectional"))
      (node (ref "R22") (pin "2") (pinfunction "2_2") (pintype "passive"))
      (node (ref "R23") (pin "1") (pinfunction "1_1") (pintype "passive"))
    )
    (net (code "85") (name "Net-(LDO_6-NR)") (class "Default")
      (node (ref "C76") (pin "1") (pinfunction "1_1") (pintype "passive"))
      (node (ref "LDO_6") (pin "6") (pinfunction "NR_6") (pintype "bidirectional"))
    )
    (net (code "86") (name "Net-(LDO_7-FB{slash}SNS)") (class "Default")
      (node (ref "C81") (pin "1") (pinfunction "1_1") (pintype "passive"))
      (node (ref "LDO_7") (pin "3") (pinfunction "FB/SNS_3") (pintype "bidirectional"))
      (node (ref "R25") (pin "2") (pinfunction "2_2") (pintype "passive"))
      (node (ref "R26") (pin "1") (pinfunction "1_1") (pintype "passive"))
    )
    (net (code "87") (name "Net-(LDO_7-NR)") (class "Default")
      (node (ref "C80") (pin "1") (pinfunction "1_1") (pintype "passive"))
      (node (ref "LDO_7") (pin "6") (pinfunction "NR_6") (pintype "bidirectional"))
    )
    (net (code "88") (name "Net-(LDO_8-FB{slash}SNS)") (class "Default")
      (node (ref "C85") (pin "1") (pinfunction "1_1") (pintype "passive"))
      (node (ref "LDO_8") (pin "3") (pinfunction "FB/SNS_3") (pintype "bidirectional"))
      (node (ref "R28") (pin "2") (pinfunction "2_2") (pintype "passive"))
      (node (ref "R29") (pin "1") (pinfunction "1_1") (pintype "passive"))
    )
    (net (code "89") (name "Net-(LDO_8-NR)") (class "Default")
      (node (ref "C84") (pin "1") (pinfunction "1_1") (pintype "passive"))
      (node (ref "LDO_8") (pin "6") (pinfunction "NR_6") (pintype "bidirectional"))
    )
    (net (code "90") (name "Net-(LDO_9-FB{slash}SNS)") (class "Default")
      (node (ref "C89") (pin "1") (pinfunction "1_1") (pintype "passive"))
      (node (ref "LDO_9") (pin "3") (pinfunction "FB/SNS_3") (pintype "bidirectional"))
      (node (ref "R31") (pin "2") (pinfunction "2_2") (pintype "passive"))
      (node (ref "R32") (pin "1") (pinfunction "1_1") (pintype "passive"))
    )
    (net (code "91") (name "Net-(LDO_9-NR)") (class "Default")
      (node (ref "C88") (pin "1") (pinfunction "1_1") (pintype "passive"))
      (node (ref "LDO_9") (pin "6") (pinfunction "NR_6") (pintype "bidirectional"))
    )
    (net (code "92") (name "Net-(LDO_10-FB{slash}SNS)") (class "Default")
      (node (ref "C93") (pin "1") (pinfunction "1_1") (pintype "passive"))
      (node (ref "LDO_10") (pin "3") (pinfunction "FB/SNS_3") (pintype "bidirectional"))
      (node (ref "R34") (pin "2") (pinfunction "2_2") (pintype "passive"))
      (node (ref "R35") (pin "1") (pinfunction "1_1") (pintype "passive"))
    )
    (net (code "93") (name "Net-(LDO_10-NR)") (class "Default")
      (node (ref "C92") (pin "1") (pinfunction "1_1") (pintype "passive"))
      (node (ref "LDO_10") (pin "6") (pinfunction "NR_6") (pintype "bidirectional"))
    )
    (net (code "94") (name "Net-(LDO_11-FB{slash}SNS)") (class "Default")
      (node (ref "C97") (pin "1") (pinfunction "1_1") (pintype "passive"))
      (node (ref "LDO_11") (pin "3") (pinfunction "FB/SNS_3") (pintype "bidirectional"))
      (node (ref "R37") (pin "2") (pinfunction "2_2") (pintype "passive"))
      (node (ref "R38") (pin "1") (pinfunction "1_1") (pintype "passive"))
    )
    (net (code "95") (name "Net-(LDO_11-NR)") (class "Default")
      (node (ref "C96") (pin "1") (pinfunction "1_1") (pintype "passive"))
      (node (ref "LDO_11") (pin "6") (pinfunction "NR_6") (pintype "bidirectional"))
    )
    (net (code "96") (name "Net-(LED1-PadA)") (class "Default")
      (node (ref "LED1") (pin "A") (pinfunction "A_A") (pintype "passive"))
      (node (ref "R201") (pin "1") (pinfunction "1_1") (pintype "passive"))
    )
    (net (code "97") (name "Net-(LNA_1-RF_IN)") (class "Default")
      (node (ref "C1") (pin "2") (pinfunction "2_2") (pintype "passive"))
      (node (ref "LNA_1") (pin "3") (pinfunction "RF_IN_3") (pintype "bidirectional"))
    )
    (net (code "98") (name "Net-(LNA_1-RF_OUT)") (class "Default")
      (node (ref "C4") (pin "1") (pinfunction "1_1") (pintype "passive"))
      (node (ref "L1") (pin "1") (pinfunction "1_1") (pintype "passive"))
      (node (ref "LNA_1") (pin "1") (pinfunction "RF_OUT_1") (pintype "bidirectional"))
    )
    (net (code "99") (name "Net-(LNA_2-RF_IN)") (class "Default")
      (node (ref "C5") (pin "2") (pinfunction "2_2") (pintype "passive"))
      (node (ref "LNA_2") (pin "3") (pinfunction "RF_IN_3") (pintype "bidirectional"))
    )
    (net (code "100") (name "Net-(LNA_2-RF_OUT)") (class "Default")
      (node (ref "C8") (pin "2") (pinfunction "2_2") (pintype "passive"))
      (node (ref "L4") (pin "1") (pinfunction "1_1") (pintype "passive"))
      (node (ref "LNA_2") (pin "1") (pinfunction "RF_OUT_1") (pintype "bidirectional"))
    )
    (net (code "101") (name "Net-(LNA_3-RF_IN)") (class "Default")
      (node (ref "C9") (pin "2") (pinfunction "2_2") (pintype "passive"))
      (node (ref "LNA_3") (pin "3") (pinfunction "RF_IN_3") (pintype "bidirectional"))
    )
    (net (code "102") (name "Net-(LNA_3-RF_OUT)") (class "Default")
      (node (ref "C12") (pin "1") (pinfunction "1_1") (pintype "passive"))
      (node (ref "L7") (pin "2") (pinfunction "2_2") (pintype "passive"))
      (node (ref "LNA_3") (pin "1") (pinfunction "RF_OUT_1") (pintype "bidirectional"))
    )
    (net (code "103") (name "Net-(LNA_4-RF_IN)") (class "Default")
      (node (ref "C14") (pin "2") (pinfunction "2_2") (pintype "passive"))
      (node (ref "LNA_4") (pin "3") (pinfunction "RF_IN_3") (pintype "bidirectional"))
    )
    (net (code "104") (name "Net-(LNA_4-RF_OUT)") (class "Default")
      (node (ref "C17") (pin "1") (pinfunction "1_1") (pintype "passive"))
      (node (ref "L10") (pin "1") (pinfunction "1_1") (pintype "passive"))
      (node (ref "LNA_4") (pin "1") (pinfunction "RF_OUT_1") (pintype "bidirectional"))
    )
    (net (code "105") (name "Net-(LNA_5-RF_IN)") (class "Default")
      (node (ref "C18") (pin "2") (pinfunction "2_2") (pintype "passive"))
      (node (ref "LNA_5") (pin "3") (pinfunction "RF_IN_3") (pintype "bidirectional"))
    )
    (net (code "106") (name "Net-(LNA_5-RF_OUT)") (class "Default")
      (node (ref "C21") (pin "1") (pinfunction "1_1") (pintype "passive"))
      (node (ref "L11") (pin "1") (pinfunction "1_1") (pintype "passive"))
      (node (ref "LNA_5") (pin "1") (pinfunction "RF_OUT_1") (pintype "bidirectional"))
    )
    (net (code "107") (name "Net-(LNA_6-RF_IN)") (class "Default")
      (node (ref "C22") (pin "2") (pinfunction "2_2") (pintype "passive"))
      (node (ref "LNA_6") (pin "3") (pinfunction "RF_IN_3") (pintype "bidirectional"))
    )
    (net (code "108") (name "Net-(LNA_6-RF_OUT)") (class "Default")
      (node (ref "C25") (pin "1") (pinfunction "1_1") (pintype "passive"))
      (node (ref "L12") (pin "2") (pinfunction "2_2") (pintype "passive"))
      (node (ref "LNA_6") (pin "1") (pinfunction "RF_OUT_1") (pintype "bidirectional"))
    )
    (net (code "109") (name "Net-(LNA_7-RF_IN)") (class "Default")
      (node (ref "C26") (pin "2") (pinfunction "2_2") (pintype "passive"))
      (node (ref "LNA_7") (pin "3") (pinfunction "RF_IN_3") (pintype "bidirectional"))
    )
    (net (code "110") (name "Net-(LNA_7-RF_OUT)") (class "Default")
      (node (ref "C29") (pin "1") (pinfunction "1_1") (pintype "passive"))
      (node (ref "L13") (pin "1") (pinfunction "1_1") (pintype "passive"))
      (node (ref "LNA_7") (pin "1") (pinfunction "RF_OUT_1") (pintype "bidirectional"))
    )
    (net (code "111") (name "Net-(LNA_8-RF_IN)") (class "Default")
      (node (ref "C30") (pin "2") (pinfunction "2_2") (pintype "passive"))
      (node (ref "LNA_8") (pin "3") (pinfunction "RF_IN_3") (pintype "bidirectional"))
    )
    (net (code "112") (name "Net-(LNA_8-RF_OUT)") (class "Default")
      (node (ref "C33") (pin "1") (pinfunction "1_1") (pintype "passive"))
      (node (ref "L14") (pin "1") (pinfunction "1_1") (pintype "passive"))
      (node (ref "LNA_8") (pin "1") (pinfunction "RF_OUT_1") (pintype "bidirectional"))
    )
    (net (code "113") (name "Net-(LNA_9-RF_IN)") (class "Default")
      (node (ref "C34") (pin "2") (pinfunction "2_2") (pintype "passive"))
      (node (ref "LNA_9") (pin "3") (pinfunction "RF_IN_3") (pintype "bidirectional"))
    )
    (net (code "114") (name "Net-(LNA_9-RF_OUT)") (class "Default")
      (node (ref "C37") (pin "1") (pinfunction "1_1") (pintype "passive"))
      (node (ref "L15") (pin "1") (pinfunction "1_1") (pintype "passive"))
      (node (ref "LNA_9") (pin "1") (pinfunction "RF_OUT_1") (pintype "bidirectional"))
    )
    (net (code "115") (name "Net-(LNA_10-RF_IN)") (class "Default")
      (node (ref "C57") (pin "2") (pinfunction "2_2") (pintype "passive"))
      (node (ref "LNA_10") (pin "3") (pinfunction "RF_IN_3") (pintype "bidirectional"))
    )
    (net (code "116") (name "Net-(LNA_10-RF_OUT)") (class "Default")
      (node (ref "C42") (pin "1") (pinfunction "1_1") (pintype "passive"))
      (node (ref "L18") (pin "1") (pinfunction "1_1") (pintype "passive"))
      (node (ref "LNA_10") (pin "1") (pinfunction "RF_OUT_1") (pintype "bidirectional"))
    )
    (net (code "117") (name "Net-(LNA_11-RF_IN)") (class "Default")
      (node (ref "C109") (pin "2") (pinfunction "2_2") (pintype "passive"))
      (node (ref "LNA_11") (pin "3") (pinfunction "RF_IN_3") (pintype "bidirectional"))
    )
    (net (code "118") (name "Net-(LNA_11-RF_OUT)") (class "Default")
      (node (ref "C110") (pin "1") (pinfunction "1_1") (pintype "passive"))
      (node (ref "L21") (pin "1") (pinfunction "1_1") (pintype "passive"))
      (node (ref "LNA_11") (pin "1") (pinfunction "RF_OUT_1") (pintype "bidirectional"))
    )
    (net (code "119") (name "Net-(R5-Pad2)") (class "Default")
      (node (ref "R5") (pin "2") (pinfunction "2_2") (pintype "passive"))
      (node (ref "X25") (pin "1") (pinfunction "1_1") (pintype "passive"))
    )
    (net (code "120") (name "Net-(SAW_1-INPUT)") (class "Default")
      (node (ref "SAW_1") (pin "1") (pinfunction "INPUT_1") (pintype "bidirectional"))
      (node (ref "X1") (pin "1") (pinfunction "1_1") (pintype "passive"))
    )
    (net (code "121") (name "Net-(SAW_1-OUTPUT)") (class "Default")
      (node (ref "C1") (pin "1") (pinfunction "1_1") (pintype "passive"))
      (node (ref "SAW_1") (pin "8") (pinfunction "OUTPUT_8") (pintype "bidirectional"))
      (node (ref "X2") (pin "1") (pinfunction "1_1") (pintype "passive"))
    )
    (net (code "122") (name "Net-(SAW_2-INPUT)") (class "Default")
      (node (ref "C4") (pin "2") (pinfunction "2_2") (pintype "passive"))
      (node (ref "L2") (pin "2") (pinfunction "2_2") (pintype "passive"))
      (node (ref "SAW_2") (pin "2") (pinfunction "INPUT_2") (pintype "bidirectional"))
      (node (ref "X3") (pin "1") (pinfunction "1_1") (pintype "passive"))
    )
    (net (code "123") (name "Net-(SAW_2-OUTPUT)") (class "Default")
      (node (ref "C5") (pin "1") (pinfunction "1_1") (pintype "passive"))
      (node (ref "L3") (pin "2") (pinfunction "2_2") (pintype "passive"))
      (node (ref "SAW_2") (pin "6") (pinfunction "OUTPUT_6") (pintype "bidirectional"))
      (node (ref "X4") (pin "1") (pinfunction "1_1") (pintype "passive"))
    )
    (net (code "124") (name "Net-(SAW_3-INPUT)") (class "Default")
      (node (ref "C8") (pin "1") (pinfunction "1_1") (pintype "passive"))
      (node (ref "L5") (pin "2") (pinfunction "2_2") (pintype "passive"))
      (node (ref "SAW_3") (pin "2") (pinfunction "INPUT_2") (pintype "bidirectional"))
      (node (ref "X5") (pin "1") (pinfunction "1_1") (pintype "passive"))
    )
    (net (code "125") (name "Net-(SAW_3-OUTPUT)") (class "Default")
      (node (ref "C9") (pin "1") (pinfunction "1_1") (pintype "passive"))
      (node (ref "L6") (pin "2") (pinfunction "2_2") (pintype "passive"))
      (node (ref "SAW_3") (pin "6") (pinfunction "OUTPUT_6") (pintype "bidirectional"))
      (node (ref "X6") (pin "1") (pinfunction "1_1") (pintype "passive"))
    )
    (net (code "126") (name "Net-(SAW_4-INPUT)") (class "Default")
      (node (ref "C12") (pin "2") (pinfunction "2_2") (pintype "passive"))
      (node (ref "L8") (pin "2") (pinfunction "2_2") (pintype "passive"))
      (node (ref "SAW_4") (pin "2") (pinfunction "INPUT_2") (pintype "bidirectional"))
      (node (ref "X7") (pin "1") (pinfunction "1_1") (pintype "passive"))
    )
    (net (code "127") (name "Net-(SAW_4-OUTPUT)") (class "Default")
      (node (ref "C13") (pin "1") (pinfunction "1_1") (pintype "passive"))
      (node (ref "L9") (pin "2") (pinfunction "2_2") (pintype "passive"))
      (node (ref "SAW_4") (pin "6") (pinfunction "OUTPUT_6") (pintype "bidirectional"))
    )
    (net (code "128") (name "Net-(SAW_5-INPUT)") (class "Default")
      (node (ref "C17") (pin "2") (pinfunction "2_2") (pintype "passive"))
      (node (ref "SAW_5") (pin "2") (pinfunction "INPUT_2") (pintype "bidirectional"))
      (node (ref "X10") (pin "1") (pinfunction "1_1") (pintype "passive"))
    )
    (net (code "129") (name "Net-(SAW_5-OUTPUT)") (class "Default")
      (node (ref "C18") (pin "1") (pinfunction "1_1") (pintype "passive"))
      (node (ref "SAW_5") (pin "6") (pinfunction "OUTPUT_6") (pintype "bidirectional"))
      (node (ref "X11") (pin "1") (pinfunction "1_1") (pintype "passive"))
    )
    (net (code "130") (name "Net-(SAW_6-INPUT)") (class "Default")
      (node (ref "C21") (pin "2") (pinfunction "2_2") (pintype "passive"))
      (node (ref "SAW_6") (pin "2") (pinfunction "INPUT_2") (pintype "bidirectional"))
      (node (ref "X12") (pin "1") (pinfunction "1_1") (pintype "passive"))
    )
    (net (code "131") (name "Net-(SAW_6-OUTPUT)") (class "Default")
      (node (ref "C22") (pin "1") (pinfunction "1_1") (pintype "passive"))
      (node (ref "SAW_6") (pin "6") (pinfunction "OUTPUT_6") (pintype "bidirectional"))
      (node (ref "X13") (pin "1") (pinfunction "1_1") (pintype "passive"))
    )
    (net (code "132") (name "Net-(SAW_7-INPUT)") (class "Default")
      (node (ref "C25") (pin "2") (pinfunction "2_2") (pintype "passive"))
      (node (ref "SAW_7") (pin "2") (pinfunction "INPUT_2") (pintype "bidirectional"))
      (node (ref "X14") (pin "1") (pinfunction "1_1") (pintype "passive"))
    )
    (net (code "133") (name "Net-(SAW_7-OUTPUT)") (class "Default")
      (node (ref "SAW_7") (pin "6") (pinfunction "OUTPUT_6") (pintype "bidirectional"))
      (node (ref "SAW_8") (pin "2") (pinfunction "INPUT_2") (pintype "bidirectional"))
      (node (ref "X15") (pin "1") (pinfunction "1_1") (pintype "passive"))
    )
    (net (code "134") (name "Net-(SAW_9-INPUT)") (class "Default")
      (node (ref "C29") (pin "2") (pinfunction "2_2") (pintype "passive"))
      (node (ref "SAW_9") (pin "2") (pinfunction "INPUT_2") (pintype "bidirectional"))
      (node (ref "X18") (pin "1") (pinfunction "1_1") (pintype "passive"))
    )
    (net (code "135") (name "Net-(SAW_9-OUTPUT)") (class "Default")
      (node (ref "C30") (pin "1") (pinfunction "1_1") (pintype "passive"))
      (node (ref "SAW_9") (pin "5") (pinfunction "OUTPUT_5") (pintype "bidirectional"))
      (node (ref "X19") (pin "1") (pinfunction "1_1") (pintype "passive"))
    )
    (net (code "136") (name "Net-(SAW_10-INPUT)") (class "Default")
      (node (ref "C33") (pin "2") (pinfunction "2_2") (pintype "passive"))
      (node (ref "SAW_10") (pin "2") (pinfunction "INPUT_2") (pintype "bidirectional"))
      (node (ref "X20") (pin "1") (pinfunction "1_1") (pintype "passive"))
    )
    (net (code "137") (name "Net-(SAW_10-OUTPUT)") (class "Default")
      (node (ref "C34") (pin "1") (pinfunction "1_1") (pintype "passive"))
      (node (ref "SAW_10") (pin "5") (pinfunction "OUTPUT_5") (pintype "bidirectional"))
      (node (ref "X21") (pin "1") (pinfunction "1_1") (pintype "passive"))
    )
    (net (code "138") (name "Net-(SAW_11-INPUT)") (class "Default")
      (node (ref "C37") (pin "2") (pinfunction "2_2") (pintype "passive"))
      (node (ref "SAW_11") (pin "2") (pinfunction "INPUT_2") (pintype "bidirectional"))
      (node (ref "X22") (pin "1") (pinfunction "1_1") (pintype "passive"))
    )
    (net (code "139") (name "Net-(SAW_11-OUTPUT)") (class "Default")
      (node (ref "SAW_11") (pin "5") (pinfunction "OUTPUT_5") (pintype "bidirectional"))
      (node (ref "SAW_12") (pin "2") (pinfunction "INPUT_2") (pintype "bidirectional"))
      (node (ref "X23") (pin "1") (pinfunction "1_1") (pintype "passive"))
    )
    (net (code "140") (name "unconnected-(IC58-ILIM-Pad6)") (class "Default")
      (node (ref "IC58") (pin "6") (pinfunction "ILIM_6") (pintype "bidirectional"))
    )
    (net (code "141") (name "unconnected-(IC58-ISHARE-Pad25)") (class "Default")
      (node (ref "IC58") (pin "25") (pinfunction "ISHARE_25") (pintype "bidirectional"))
    )
    (net (code "142") (name "unconnected-(IC58-OCP_SEL-Pad4)") (class "Default")
      (node (ref "IC58") (pin "4") (pinfunction "OCP_SEL_4") (pintype "bidirectional"))
    )
    (net (code "143") (name "unconnected-(IC58-SS{slash}TR-Pad28)") (class "Default")
      (node (ref "IC58") (pin "28") (pinfunction "SS/TR_28") (pintype "bidirectional"))
    )
    (net (code "144") (name "unconnected-(IC58-SYNC_OUT-Pad7)") (class "Default")
      (node (ref "IC58") (pin "7") (pinfunction "SYNC_OUT_7") (pintype "bidirectional"))
    )
  )
)
